# SCH_esp32-8z_230302_2023-04-26.net
KiCad netlist of a schematic drawn in EasyEDA
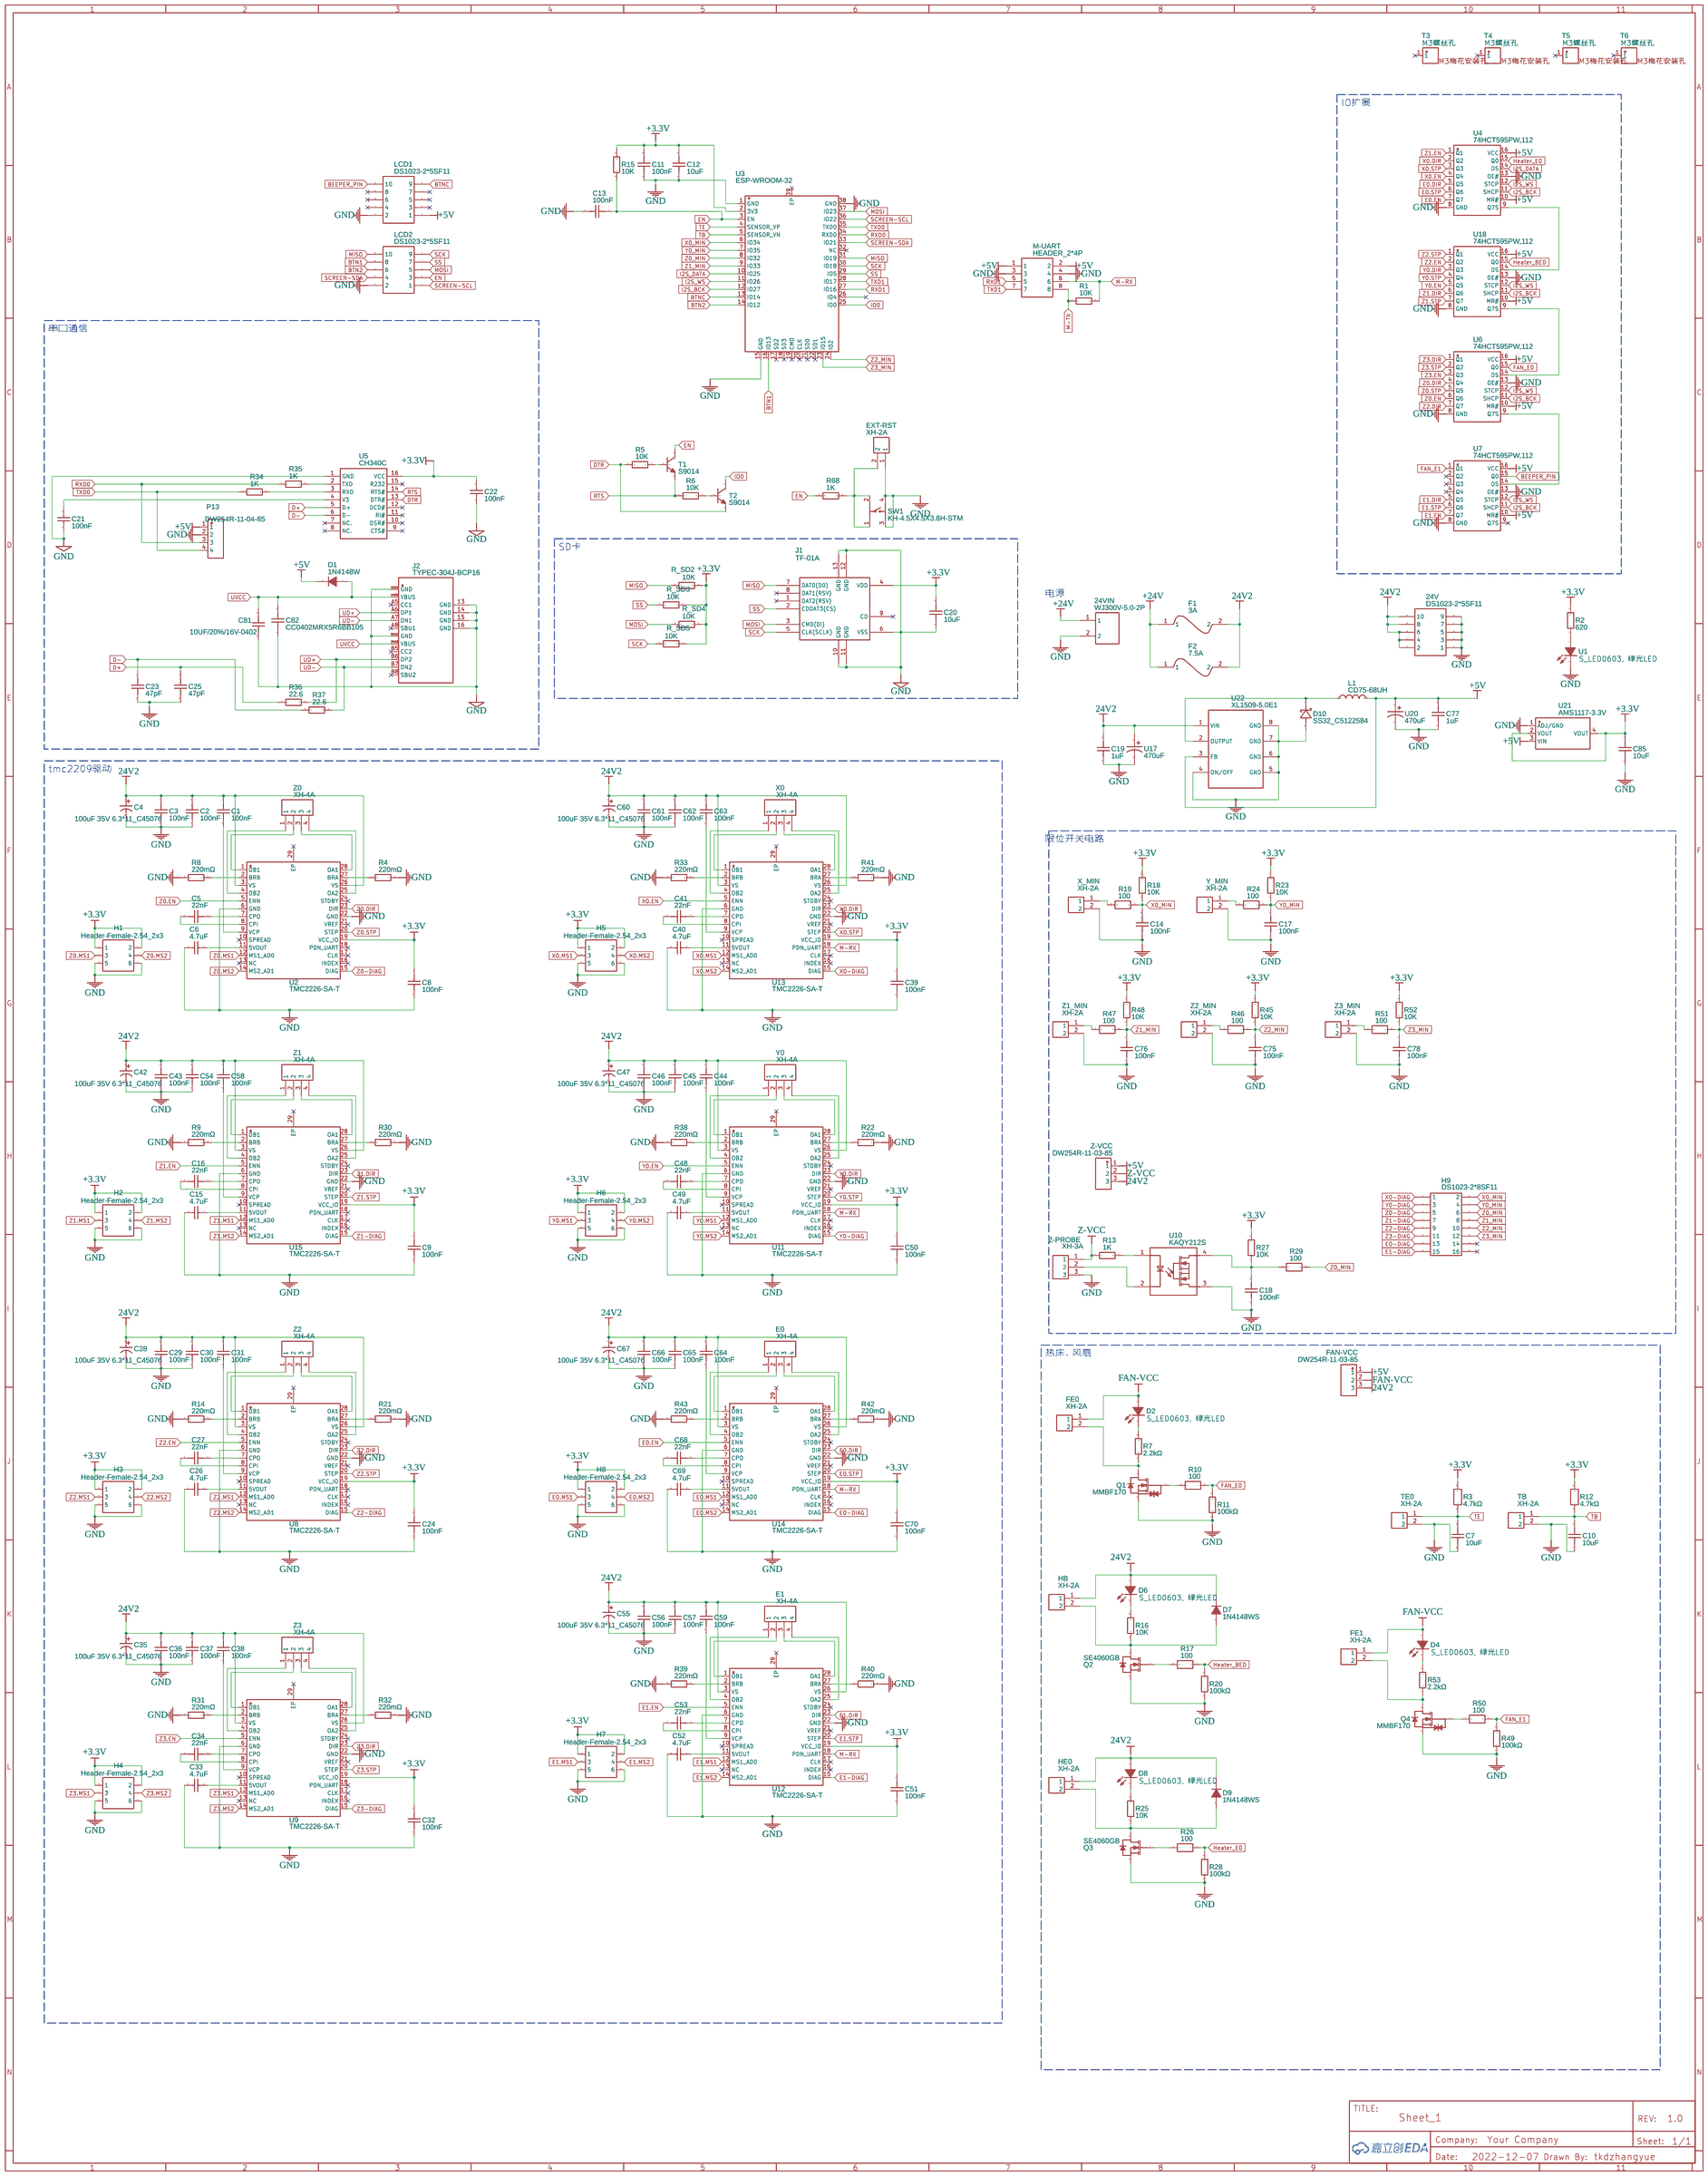
[diagram p0: schematic sheet]

(export (version "E")
  (design (tool "Eeschema 10.0.6"))
  (components
    (comp (ref "24V")
      (value "DS1023-2*5SF11")
      (fields (field (name "BOM_Supplier Part") "C92270"))
      (libsource (lib "") (part "DS1023-2*5SF11_1"))
    )
    (comp (ref "24VIN")
      (value "WJ300V-5.0-2P")
      (fields (field (name "BOM_Supplier Part") "C8385"))
      (libsource (lib "") (part "WJ300V-5.0-2P"))
    )
    (comp (ref "C1")
      (value "100nF")
      (fields
        (field (name "BOM_Manufacturer Part") "06031C104KAT2A")
        (field (name "BOM_Supplier Part") "C2167300")
      )
      (libsource (lib "") (part "06031C104KAT2A_1"))
    )
    (comp (ref "C2")
      (value "100nF")
      (fields
        (field (name "BOM_Manufacturer Part") "06031C104KAT2A")
        (field (name "BOM_Supplier Part") "C2167300")
      )
      (libsource (lib "") (part "06031C104KAT2A"))
    )
    (comp (ref "C3")
      (value "100nF")
      (fields
        (field (name "BOM_Manufacturer Part") "06031C104KAT2A")
        (field (name "BOM_Supplier Part") "C2167300")
      )
      (libsource (lib "") (part "06031C104KAT2A"))
    )
    (comp (ref "C4")
      (value "100uF 35V 6.3*11_C45076")
      (fields
        (field (name "BOM_Manufacturer Part") "100uF 35V 6.3*11")
        (field (name "BOM_Supplier Part") "C45076")
      )
      (libsource (lib "") (part "100uF 35V 6.3*11_C45076"))
    )
    (comp (ref "C5")
      (value "22nF")
      (fields
        (field (name "BOM_Manufacturer Part") "CC0603JRX7R7BB223")
        (field (name "BOM_Supplier Part") "C519532")
      )
      (libsource (lib "") (part "CC0603JRX7R7BB223"))
    )
    (comp (ref "C6")
      (value "4.7uF")
      (fields
        (field (name "BOM_Manufacturer Part") "CC0603KRX5R6BB475")
        (field (name "BOM_Supplier Part") "C109456")
      )
      (libsource (lib "") (part "CC0603KRX5R6BB475"))
    )
    (comp (ref "C7")
      (value "10uF")
      (fields (field (name "BOM_Supplier Part") "C15415"))
      (libsource (lib "") (part "10UF"))
    )
    (comp (ref "C8")
      (value "100nF")
      (fields
        (field (name "BOM_Manufacturer Part") "06031C104KAT2A")
        (field (name "BOM_Supplier Part") "C2167300")
      )
      (libsource (lib "") (part "06031C104KAT2A_1"))
    )
    (comp (ref "C9")
      (value "100nF")
      (fields
        (field (name "BOM_Manufacturer Part") "06031C104KAT2A")
        (field (name "BOM_Supplier Part") "C2167300")
      )
      (libsource (lib "") (part "06031C104KAT2A_1"))
    )
    (comp (ref "C10")
      (value "10uF")
      (fields (field (name "BOM_Supplier Part") "C15415"))
      (libsource (lib "") (part "10UF"))
    )
    (comp (ref "C11")
      (value "100nF")
      (fields
        (field (name "BOM_Manufacturer Part") "06031C104KAT2A")
        (field (name "BOM_Supplier Part") "C2167300")
      )
      (libsource (lib "") (part "06031C104KAT2A"))
    )
    (comp (ref "C12")
      (value "10uF")
      (fields
        (field (name "BOM_Manufacturer Part") "TCC0603X5R106K100CT")
        (field (name "BOM_Supplier Part") "C380314")
      )
      (libsource (lib "") (part "TCC0603X5R106K100CT"))
    )
    (comp (ref "C13")
      (value "100nF")
      (fields
        (field (name "BOM_Manufacturer Part") "06031C104KAT2A")
        (field (name "BOM_Supplier Part") "C2167300")
      )
      (libsource (lib "") (part "06031C104KAT2A_2"))
    )
    (comp (ref "C14")
      (value "100nF")
      (fields
        (field (name "BOM_Manufacturer Part") "06031C104KAT2A")
        (field (name "BOM_Supplier Part") "C2167300")
      )
      (libsource (lib "") (part "06031C104KAT2A"))
    )
    (comp (ref "C15")
      (value "4.7uF")
      (fields
        (field (name "BOM_Manufacturer Part") "CC0603KRX5R6BB475")
        (field (name "BOM_Supplier Part") "C109456")
      )
      (libsource (lib "") (part "CC0603KRX5R6BB475"))
    )
    (comp (ref "C16")
      (value "22nF")
      (fields
        (field (name "BOM_Manufacturer Part") "CC0603JRX7R7BB223")
        (field (name "BOM_Supplier Part") "C519532")
      )
      (libsource (lib "") (part "CC0603JRX7R7BB223"))
    )
    (comp (ref "C17")
      (value "100nF")
      (fields
        (field (name "BOM_Manufacturer Part") "06031C104KAT2A")
        (field (name "BOM_Supplier Part") "C2167300")
      )
      (libsource (lib "") (part "06031C104KAT2A"))
    )
    (comp (ref "C18")
      (value "100nF")
      (fields
        (field (name "BOM_Manufacturer Part") "06031C104KAT2A")
        (field (name "BOM_Supplier Part") "C2167300")
      )
      (libsource (lib "") (part "06031C104KAT2A"))
    )
    (comp (ref "C19")
      (value "1uF")
      (fields
        (field (name "BOM_Manufacturer Part") "0603B105K500NT")
        (field (name "BOM_Supplier Part") "C90540")
      )
      (libsource (lib "") (part "0603B105K500NT"))
    )
    (comp (ref "C20")
      (value "10uF")
      (fields
        (field (name "BOM_Manufacturer Part") "TCC0603X5R106K100CT")
        (field (name "BOM_Supplier Part") "C380314")
      )
      (libsource (lib "") (part "TCC0603X5R106K100CT"))
    )
    (comp (ref "C21")
      (value "100nF")
      (fields
        (field (name "BOM_Manufacturer Part") "0402YD104KAT2A")
        (field (name "BOM_Supplier Part") "C142647")
      )
      (libsource (lib "") (part "0402YD104KAT2A"))
    )
    (comp (ref "C22")
      (value "100nF")
      (fields
        (field (name "BOM_Manufacturer Part") "0402YD104KAT2A")
        (field (name "BOM_Supplier Part") "C142647")
      )
      (libsource (lib "") (part "0402YD104KAT2A"))
    )
    (comp (ref "C23")
      (value "47pF")
      (fields
        (field (name "BOM_Manufacturer Part") "0603N470F101")
        (field (name "BOM_Supplier Part") "C152905")
      )
      (libsource (lib "") (part "0603N470F101"))
    )
    (comp (ref "C24")
      (value "100nF")
      (fields
        (field (name "BOM_Manufacturer Part") "06031C104KAT2A")
        (field (name "BOM_Supplier Part") "C2167300")
      )
      (libsource (lib "") (part "06031C104KAT2A_1"))
    )
    (comp (ref "C25")
      (value "47pF")
      (fields
        (field (name "BOM_Manufacturer Part") "0603N470F101")
        (field (name "BOM_Supplier Part") "C152905")
      )
      (libsource (lib "") (part "0603N470F101"))
    )
    (comp (ref "C26")
      (value "4.7uF")
      (fields
        (field (name "BOM_Manufacturer Part") "CC0603KRX5R6BB475")
        (field (name "BOM_Supplier Part") "C109456")
      )
      (libsource (lib "") (part "CC0603KRX5R6BB475"))
    )
    (comp (ref "C27")
      (value "22nF")
      (fields
        (field (name "BOM_Manufacturer Part") "CC0603JRX7R7BB223")
        (field (name "BOM_Supplier Part") "C519532")
      )
      (libsource (lib "") (part "CC0603JRX7R7BB223"))
    )
    (comp (ref "C28")
      (value "100uF 35V 6.3*11_C45076")
      (fields
        (field (name "BOM_Manufacturer Part") "100uF 35V 6.3*11")
        (field (name "BOM_Supplier Part") "C45076")
      )
      (libsource (lib "") (part "100uF 35V 6.3*11_C45076"))
    )
    (comp (ref "C29")
      (value "100nF")
      (fields
        (field (name "BOM_Manufacturer Part") "06031C104KAT2A")
        (field (name "BOM_Supplier Part") "C2167300")
      )
      (libsource (lib "") (part "06031C104KAT2A"))
    )
    (comp (ref "C30")
      (value "100nF")
      (fields
        (field (name "BOM_Manufacturer Part") "06031C104KAT2A")
        (field (name "BOM_Supplier Part") "C2167300")
      )
      (libsource (lib "") (part "06031C104KAT2A"))
    )
    (comp (ref "C31")
      (value "100nF")
      (fields
        (field (name "BOM_Manufacturer Part") "06031C104KAT2A")
        (field (name "BOM_Supplier Part") "C2167300")
      )
      (libsource (lib "") (part "06031C104KAT2A_1"))
    )
    (comp (ref "C32")
      (value "100nF")
      (fields
        (field (name "BOM_Manufacturer Part") "06031C104KAT2A")
        (field (name "BOM_Supplier Part") "C2167300")
      )
      (libsource (lib "") (part "06031C104KAT2A_1"))
    )
    (comp (ref "C33")
      (value "4.7uF")
      (fields
        (field (name "BOM_Manufacturer Part") "CC0603KRX5R6BB475")
        (field (name "BOM_Supplier Part") "C109456")
      )
      (libsource (lib "") (part "CC0603KRX5R6BB475"))
    )
    (comp (ref "C34")
      (value "22nF")
      (fields
        (field (name "BOM_Manufacturer Part") "CC0603JRX7R7BB223")
        (field (name "BOM_Supplier Part") "C519532")
      )
      (libsource (lib "") (part "CC0603JRX7R7BB223"))
    )
    (comp (ref "C35")
      (value "100uF 35V 6.3*11_C45076")
      (fields
        (field (name "BOM_Manufacturer Part") "100uF 35V 6.3*11")
        (field (name "BOM_Supplier Part") "C45076")
      )
      (libsource (lib "") (part "100uF 35V 6.3*11_C45076"))
    )
    (comp (ref "C36")
      (value "100nF")
      (fields
        (field (name "BOM_Manufacturer Part") "06031C104KAT2A")
        (field (name "BOM_Supplier Part") "C2167300")
      )
      (libsource (lib "") (part "06031C104KAT2A"))
    )
    (comp (ref "C37")
      (value "100nF")
      (fields
        (field (name "BOM_Manufacturer Part") "06031C104KAT2A")
        (field (name "BOM_Supplier Part") "C2167300")
      )
      (libsource (lib "") (part "06031C104KAT2A"))
    )
    (comp (ref "C38")
      (value "100nF")
      (fields
        (field (name "BOM_Manufacturer Part") "06031C104KAT2A")
        (field (name "BOM_Supplier Part") "C2167300")
      )
      (libsource (lib "") (part "06031C104KAT2A_1"))
    )
    (comp (ref "C39")
      (value "100nF")
      (fields
        (field (name "BOM_Manufacturer Part") "06031C104KAT2A")
        (field (name "BOM_Supplier Part") "C2167300")
      )
      (libsource (lib "") (part "06031C104KAT2A_1"))
    )
    (comp (ref "C40")
      (value "4.7uF")
      (fields
        (field (name "BOM_Manufacturer Part") "CC0603KRX5R6BB475")
        (field (name "BOM_Supplier Part") "C109456")
      )
      (libsource (lib "") (part "CC0603KRX5R6BB475"))
    )
    (comp (ref "C41")
      (value "22nF")
      (fields
        (field (name "BOM_Manufacturer Part") "CC0603JRX7R7BB223")
        (field (name "BOM_Supplier Part") "C519532")
      )
      (libsource (lib "") (part "CC0603JRX7R7BB223"))
    )
    (comp (ref "C42")
      (value "100uF 35V 6.3*11_C45076")
      (fields
        (field (name "BOM_Manufacturer Part") "100uF 35V 6.3*11")
        (field (name "BOM_Supplier Part") "C45076")
      )
      (libsource (lib "") (part "100uF 35V 6.3*11_C45076"))
    )
    (comp (ref "C43")
      (value "100nF")
      (fields
        (field (name "BOM_Manufacturer Part") "06031C104KAT2A")
        (field (name "BOM_Supplier Part") "C2167300")
      )
      (libsource (lib "") (part "06031C104KAT2A"))
    )
    (comp (ref "C44")
      (value "100nF")
      (fields
        (field (name "BOM_Manufacturer Part") "06031C104KAT2A")
        (field (name "BOM_Supplier Part") "C2167300")
      )
      (libsource (lib "") (part "06031C104KAT2A_1"))
    )
    (comp (ref "C45")
      (value "100nF")
      (fields
        (field (name "BOM_Manufacturer Part") "06031C104KAT2A")
        (field (name "BOM_Supplier Part") "C2167300")
      )
      (libsource (lib "") (part "06031C104KAT2A"))
    )
    (comp (ref "C46")
      (value "100nF")
      (fields
        (field (name "BOM_Manufacturer Part") "06031C104KAT2A")
        (field (name "BOM_Supplier Part") "C2167300")
      )
      (libsource (lib "") (part "06031C104KAT2A"))
    )
    (comp (ref "C47")
      (value "100uF 35V 6.3*11_C45076")
      (fields
        (field (name "BOM_Manufacturer Part") "100uF 35V 6.3*11")
        (field (name "BOM_Supplier Part") "C45076")
      )
      (libsource (lib "") (part "100uF 35V 6.3*11_C45076"))
    )
    (comp (ref "C48")
      (value "22nF")
      (fields
        (field (name "BOM_Manufacturer Part") "CC0603JRX7R7BB223")
        (field (name "BOM_Supplier Part") "C519532")
      )
      (libsource (lib "") (part "CC0603JRX7R7BB223"))
    )
    (comp (ref "C49")
      (value "4.7uF")
      (fields
        (field (name "BOM_Manufacturer Part") "CC0603KRX5R6BB475")
        (field (name "BOM_Supplier Part") "C109456")
      )
      (libsource (lib "") (part "CC0603KRX5R6BB475"))
    )
    (comp (ref "C50")
      (value "100nF")
      (fields
        (field (name "BOM_Manufacturer Part") "06031C104KAT2A")
        (field (name "BOM_Supplier Part") "C2167300")
      )
      (libsource (lib "") (part "06031C104KAT2A_1"))
    )
    (comp (ref "C51")
      (value "100nF")
      (fields
        (field (name "BOM_Manufacturer Part") "06031C104KAT2A")
        (field (name "BOM_Supplier Part") "C2167300")
      )
      (libsource (lib "") (part "06031C104KAT2A_1"))
    )
    (comp (ref "C52")
      (value "4.7uF")
      (fields
        (field (name "BOM_Manufacturer Part") "CC0603KRX5R6BB475")
        (field (name "BOM_Supplier Part") "C109456")
      )
      (libsource (lib "") (part "CC0603KRX5R6BB475"))
    )
    (comp (ref "C53")
      (value "22nF")
      (fields
        (field (name "BOM_Manufacturer Part") "CC0603JRX7R7BB223")
        (field (name "BOM_Supplier Part") "C519532")
      )
      (libsource (lib "") (part "CC0603JRX7R7BB223"))
    )
    (comp (ref "C54")
      (value "100nF")
      (fields
        (field (name "BOM_Manufacturer Part") "06031C104KAT2A")
        (field (name "BOM_Supplier Part") "C2167300")
      )
      (libsource (lib "") (part "06031C104KAT2A"))
    )
    (comp (ref "C55")
      (value "100uF 35V 6.3*11_C45076")
      (fields
        (field (name "BOM_Manufacturer Part") "100uF 35V 6.3*11")
        (field (name "BOM_Supplier Part") "C45076")
      )
      (libsource (lib "") (part "100uF 35V 6.3*11_C45076"))
    )
    (comp (ref "C56")
      (value "100nF")
      (fields
        (field (name "BOM_Manufacturer Part") "06031C104KAT2A")
        (field (name "BOM_Supplier Part") "C2167300")
      )
      (libsource (lib "") (part "06031C104KAT2A"))
    )
    (comp (ref "C57")
      (value "100nF")
      (fields
        (field (name "BOM_Manufacturer Part") "06031C104KAT2A")
        (field (name "BOM_Supplier Part") "C2167300")
      )
      (libsource (lib "") (part "06031C104KAT2A"))
    )
    (comp (ref "C58")
      (value "100nF")
      (fields
        (field (name "BOM_Manufacturer Part") "06031C104KAT2A")
        (field (name "BOM_Supplier Part") "C2167300")
      )
      (libsource (lib "") (part "06031C104KAT2A_1"))
    )
    (comp (ref "C59")
      (value "100nF")
      (fields
        (field (name "BOM_Manufacturer Part") "06031C104KAT2A")
        (field (name "BOM_Supplier Part") "C2167300")
      )
      (libsource (lib "") (part "06031C104KAT2A_1"))
    )
    (comp (ref "C60")
      (value "100uF 35V 6.3*11_C45076")
      (fields
        (field (name "BOM_Manufacturer Part") "100uF 35V 6.3*11")
        (field (name "BOM_Supplier Part") "C45076")
      )
      (libsource (lib "") (part "100uF 35V 6.3*11_C45076"))
    )
    (comp (ref "C61")
      (value "100nF")
      (fields
        (field (name "BOM_Manufacturer Part") "06031C104KAT2A")
        (field (name "BOM_Supplier Part") "C2167300")
      )
      (libsource (lib "") (part "06031C104KAT2A"))
    )
    (comp (ref "C62")
      (value "100nF")
      (fields
        (field (name "BOM_Manufacturer Part") "06031C104KAT2A")
        (field (name "BOM_Supplier Part") "C2167300")
      )
      (libsource (lib "") (part "06031C104KAT2A"))
    )
    (comp (ref "C63")
      (value "100nF")
      (fields
        (field (name "BOM_Manufacturer Part") "06031C104KAT2A")
        (field (name "BOM_Supplier Part") "C2167300")
      )
      (libsource (lib "") (part "06031C104KAT2A_1"))
    )
    (comp (ref "C64")
      (value "100nF")
      (fields
        (field (name "BOM_Manufacturer Part") "06031C104KAT2A")
        (field (name "BOM_Supplier Part") "C2167300")
      )
      (libsource (lib "") (part "06031C104KAT2A_1"))
    )
    (comp (ref "C65")
      (value "100nF")
      (fields
        (field (name "BOM_Manufacturer Part") "06031C104KAT2A")
        (field (name "BOM_Supplier Part") "C2167300")
      )
      (libsource (lib "") (part "06031C104KAT2A"))
    )
    (comp (ref "C66")
      (value "100nF")
      (fields
        (field (name "BOM_Manufacturer Part") "06031C104KAT2A")
        (field (name "BOM_Supplier Part") "C2167300")
      )
      (libsource (lib "") (part "06031C104KAT2A"))
    )
    (comp (ref "C67")
      (value "100uF 35V 6.3*11_C45076")
      (fields
        (field (name "BOM_Manufacturer Part") "100uF 35V 6.3*11")
        (field (name "BOM_Supplier Part") "C45076")
      )
      (libsource (lib "") (part "100uF 35V 6.3*11_C45076"))
    )
    (comp (ref "C68")
      (value "22nF")
      (fields
        (field (name "BOM_Manufacturer Part") "CC0603JRX7R7BB223")
        (field (name "BOM_Supplier Part") "C519532")
      )
      (libsource (lib "") (part "CC0603JRX7R7BB223"))
    )
    (comp (ref "C69")
      (value "4.7uF")
      (fields
        (field (name "BOM_Manufacturer Part") "CC0603KRX5R6BB475")
        (field (name "BOM_Supplier Part") "C109456")
      )
      (libsource (lib "") (part "CC0603KRX5R6BB475"))
    )
    (comp (ref "C70")
      (value "100nF")
      (fields
        (field (name "BOM_Manufacturer Part") "06031C104KAT2A")
        (field (name "BOM_Supplier Part") "C2167300")
      )
      (libsource (lib "") (part "06031C104KAT2A_1"))
    )
    (comp (ref "C75")
      (value "100nF")
      (fields
        (field (name "BOM_Manufacturer Part") "06031C104KAT2A")
        (field (name "BOM_Supplier Part") "C2167300")
      )
      (libsource (lib "") (part "06031C104KAT2A"))
    )
    (comp (ref "C76")
      (value "100nF")
      (fields
        (field (name "BOM_Manufacturer Part") "06031C104KAT2A")
        (field (name "BOM_Supplier Part") "C2167300")
      )
      (libsource (lib "") (part "06031C104KAT2A"))
    )
    (comp (ref "C77")
      (value "1uF")
      (fields
        (field (name "BOM_Manufacturer Part") "0603B105K500NT")
        (field (name "BOM_Supplier Part") "C90540")
      )
      (libsource (lib "") (part "0603B105K500NT"))
    )
    (comp (ref "C78")
      (value "100nF")
      (fields
        (field (name "BOM_Manufacturer Part") "06031C104KAT2A")
        (field (name "BOM_Supplier Part") "C2167300")
      )
      (libsource (lib "") (part "06031C104KAT2A"))
    )
    (comp (ref "C81")
      (value "10UF/20%/16V-0402")
      (fields
        (field (name "BOM_Manufacturer Part") "10uF/20%/16V-0402")
        (field (name "BOM_Supplier Part") "C9900005775")
      )
      (libsource (lib "") (part "10UF/20%/16V-0402"))
    )
    (comp (ref "C82")
      (value "CC0402MRX5R6BB105")
      (fields (field (name "BOM_Supplier Part") "C113791"))
      (libsource (lib "") (part "CC0402MRX5R6BB105"))
    )
    (comp (ref "C85")
      (value "10uF")
      (fields
        (field (name "BOM_Manufacturer Part") "TCC0603X5R106K100CT")
        (field (name "BOM_Supplier Part") "C380314")
      )
      (libsource (lib "") (part "TCC0603X5R106K100CT"))
    )
    (comp (ref "D1")
      (value "1N4148W")
      (fields (field (name "BOM_Supplier Part") "C179717"))
      (libsource (lib "") (part "1N4148W"))
    )
    (comp (ref "D2")
      (value "S_LED0603, 绿光LED")
      (fields (field (name "BOM_Supplier Part") "C9900025458"))
      (libsource (lib "") (part "S_LED0603, 绿光LED_1"))
    )
    (comp (ref "D4")
      (value "S_LED0603, 绿光LED")
      (fields (field (name "BOM_Supplier Part") "C9900025458"))
      (libsource (lib "") (part "S_LED0603, 绿光LED_1"))
    )
    (comp (ref "D6")
      (value "S_LED0603, 绿光LED")
      (fields (field (name "BOM_Supplier Part") "C9900025458"))
      (libsource (lib "") (part "S_LED0603, 绿光LED_1"))
    )
    (comp (ref "D7")
      (value "1N4148WS")
      (fields (field (name "BOM_Supplier Part") "C179718"))
      (libsource (lib "") (part "1N4148WS"))
    )
    (comp (ref "D8")
      (value "S_LED0603, 绿光LED")
      (fields (field (name "BOM_Supplier Part") "C9900025458"))
      (libsource (lib "") (part "S_LED0603, 绿光LED_1"))
    )
    (comp (ref "D9")
      (value "1N4148WS")
      (fields (field (name "BOM_Supplier Part") "C179718"))
      (libsource (lib "") (part "1N4148WS"))
    )
    (comp (ref "D10")
      (value "SS32_C5122584")
      (fields (field (name "BOM_Manufacturer Part") "SS32") (field (name "BOM_Supplier Part") "C5122584"))
      (libsource (lib "") (part "SS32_C5122584"))
    )
    (comp (ref "E0")
      (value "XH-4A")
      (fields (field (name "BOM_Supplier Part") "C37815"))
      (libsource (lib "") (part "XH-4A_3"))
    )
    (comp (ref "E1")
      (value "XH-4A")
      (fields (field (name "BOM_Supplier Part") "C37815"))
      (libsource (lib "") (part "XH-4A_3"))
    )
    (comp (ref "EXT-RST")
      (value "XH-2A")
      (fields (field (name "BOM_Supplier Part") "C20079"))
      (libsource (lib "") (part "XH-2A_6"))
    )
    (comp (ref "F1") (value "3A") (libsource (lib "") (part "小型汽车插片保险座")))
    (comp (ref "F2") (value "7.5A") (libsource (lib "") (part "小型汽车插片保险座")))
    (comp (ref "FAN-VCC")
      (value "DW254R-11-03-85")
      (fields (field (name "BOM_Supplier Part") "C2935897"))
      (libsource (lib "") (part "DW254R-11-03-85"))
    )
    (comp (ref "FE0")
      (value "XH-2A")
      (fields (field (name "BOM_Supplier Part") "C20079"))
      (libsource (lib "") (part "XH-2A"))
    )
    (comp (ref "FE1")
      (value "XH-2A")
      (fields (field (name "BOM_Supplier Part") "C20079"))
      (libsource (lib "") (part "XH-2A"))
    )
    (comp (ref "H1")
      (value "Header-Female-2.54_2x3")
      (fields
        (field (name "BOM_Manufacturer Part") "DS1023-2*3SF11")
        (field (name "BOM_Supplier Part") "C92272")
      )
      (libsource (lib "") (part "Header-Female-2.54_2x3"))
    )
    (comp (ref "H2")
      (value "Header-Female-2.54_2x3")
      (fields
        (field (name "BOM_Manufacturer Part") "DS1023-2*3SF11")
        (field (name "BOM_Supplier Part") "C92272")
      )
      (libsource (lib "") (part "Header-Female-2.54_2x3"))
    )
    (comp (ref "H3")
      (value "Header-Female-2.54_2x3")
      (fields
        (field (name "BOM_Manufacturer Part") "DS1023-2*3SF11")
        (field (name "BOM_Supplier Part") "C92272")
      )
      (libsource (lib "") (part "Header-Female-2.54_2x3"))
    )
    (comp (ref "H4")
      (value "Header-Female-2.54_2x3")
      (fields
        (field (name "BOM_Manufacturer Part") "DS1023-2*3SF11")
        (field (name "BOM_Supplier Part") "C92272")
      )
      (libsource (lib "") (part "Header-Female-2.54_2x3"))
    )
    (comp (ref "H5")
      (value "Header-Female-2.54_2x3")
      (fields
        (field (name "BOM_Manufacturer Part") "DS1023-2*3SF11")
        (field (name "BOM_Supplier Part") "C92272")
      )
      (libsource (lib "") (part "Header-Female-2.54_2x3"))
    )
    (comp (ref "H6")
      (value "Header-Female-2.54_2x3")
      (fields
        (field (name "BOM_Manufacturer Part") "DS1023-2*3SF11")
        (field (name "BOM_Supplier Part") "C92272")
      )
      (libsource (lib "") (part "Header-Female-2.54_2x3"))
    )
    (comp (ref "H7")
      (value "Header-Female-2.54_2x3")
      (fields
        (field (name "BOM_Manufacturer Part") "DS1023-2*3SF11")
        (field (name "BOM_Supplier Part") "C92272")
      )
      (libsource (lib "") (part "Header-Female-2.54_2x3"))
    )
    (comp (ref "H8")
      (value "Header-Female-2.54_2x3")
      (fields
        (field (name "BOM_Manufacturer Part") "DS1023-2*3SF11")
        (field (name "BOM_Supplier Part") "C92272")
      )
      (libsource (lib "") (part "Header-Female-2.54_2x3"))
    )
    (comp (ref "H9")
      (value "DS1023-2*8SF11")
      (fields (field (name "BOM_Supplier Part") "C92267"))
      (libsource (lib "") (part "DS1023-2*8SF11"))
    )
    (comp (ref "HB")
      (value "XH-2A")
      (fields (field (name "BOM_Supplier Part") "C20079"))
      (libsource (lib "") (part "XH-2A_4"))
    )
    (comp (ref "HE0")
      (value "XH-2A")
      (fields (field (name "BOM_Supplier Part") "C20079"))
      (libsource (lib "") (part "XH-2A_7"))
    )
    (comp (ref "J1")
      (value "TF-01A")
      (fields (field (name "BOM_Supplier Part") "C91145"))
      (libsource (lib "") (part "TF-01A"))
    )
    (comp (ref "J2")
      (value "TYPEC-304J-BCP16")
      (fields (field (name "BOM_Supplier Part") "C2835315"))
      (libsource (lib "") (part "TYPEC-304J-BCP16"))
    )
    (comp (ref "L1")
      (value "CD75-68UH")
      (fields (field (name "BOM_Supplier Part") "C2836693"))
      (libsource (lib "") (part "CD75-68UH"))
    )
    (comp (ref "LCD1")
      (value "DS1023-2*5SF11")
      (fields (field (name "BOM_Supplier Part") "C92270"))
      (libsource (lib "") (part "DS1023-2*5SF11"))
    )
    (comp (ref "LCD2")
      (value "DS1023-2*5SF11")
      (fields (field (name "BOM_Supplier Part") "C92270"))
      (libsource (lib "") (part "DS1023-2*5SF11"))
    )
    (comp (ref "M-UART")
      (value "HEADER_2*4P")
      (fields (field (name "BOM_Supplier Part") "C9900003187"))
      (libsource (lib "") (part "HEADER_2*4P"))
    )
    (comp (ref "P13")
      (value "DW254R-11-04-85")
      (fields (field (name "BOM_Supplier Part") "C2935898"))
      (libsource (lib "") (part "DW254R-11-04-85"))
    )
    (comp (ref "Q1")
      (value "MMBF170")
      (fields (field (name "BOM_Supplier Part") "C130879"))
      (libsource (lib "") (part "MMBF170"))
    )
    (comp (ref "Q2")
      (value "SE4060GB")
      (fields (field (name "BOM_Supplier Part") "C238624"))
      (libsource (lib "") (part "SE4060GB"))
    )
    (comp (ref "Q3")
      (value "SE4060GB")
      (fields (field (name "BOM_Supplier Part") "C238624"))
      (libsource (lib "") (part "SE4060GB"))
    )
    (comp (ref "Q4")
      (value "MMBF170")
      (fields (field (name "BOM_Supplier Part") "C130879"))
      (libsource (lib "") (part "MMBF170"))
    )
    (comp (ref "R1")
      (value "10K")
      (fields
        (field (name "BOM_Manufacturer Part") "AF0603JR-0710KL")
        (field (name "BOM_Supplier Part") "C144116")
      )
      (libsource (lib "") (part "AF0603JR-0710KL_1"))
    )
    (comp (ref "R2")
      (value "620")
      (fields
        (field (name "BOM_Manufacturer Part") "RC0603JR-07620RL")
        (field (name "BOM_Supplier Part") "C137616")
      )
      (libsource (lib "") (part "RC0603JR-07620RL"))
    )
    (comp (ref "R3")
      (value "4.7kΩ")
      (fields
        (field (name "BOM_Manufacturer Part") "RT0603FRE074K7L")
        (field (name "BOM_Supplier Part") "C700513")
      )
      (libsource (lib "") (part "RT0603FRE074K7L"))
    )
    (comp (ref "R4")
      (value "220mΩ")
      (fields
        (field (name "BOM_Manufacturer Part") "CR0603FR220P05Z")
        (field (name "BOM_Supplier Part") "C175648")
      )
      (libsource (lib "") (part "CR0603F0R22P05"))
    )
    (comp (ref "R5")
      (value "10K")
      (fields
        (field (name "BOM_Manufacturer Part") "AF0603JR-0710KL")
        (field (name "BOM_Supplier Part") "C144116")
      )
      (libsource (lib "") (part "AF0603JR-0710KL_1"))
    )
    (comp (ref "R6")
      (value "10K")
      (fields
        (field (name "BOM_Manufacturer Part") "AF0603JR-0710KL")
        (field (name "BOM_Supplier Part") "C144116")
      )
      (libsource (lib "") (part "AF0603JR-0710KL_1"))
    )
    (comp (ref "R7")
      (value "2.2kΩ")
      (fields
        (field (name "BOM_Manufacturer Part") "RMC06032.2K1%N")
        (field (name "BOM_Supplier Part") "C325591")
      )
      (libsource (lib "") (part "RMC06032.2K1%N"))
    )
    (comp (ref "R8")
      (value "220mΩ")
      (fields
        (field (name "BOM_Manufacturer Part") "CR0603FR220P05Z")
        (field (name "BOM_Supplier Part") "C175648")
      )
      (libsource (lib "") (part "CR0603F0R22P05"))
    )
    (comp (ref "R9")
      (value "220mΩ")
      (fields
        (field (name "BOM_Manufacturer Part") "CR0603FR220P05Z")
        (field (name "BOM_Supplier Part") "C175648")
      )
      (libsource (lib "") (part "CR0603F0R22P05"))
    )
    (comp (ref "R10")
      (value "100")
      (fields
        (field (name "BOM_Manufacturer Part") "AC0603DR-07100RL")
        (field (name "BOM_Supplier Part") "C227435")
      )
      (libsource (lib "") (part "AC0603DR-07100RL"))
    )
    (comp (ref "R11")
      (value "100kΩ")
      (fields
        (field (name "BOM_Manufacturer Part") "RMCF0603FT100K")
        (field (name "BOM_Supplier Part") "C237792")
      )
      (libsource (lib "") (part "RMCF0603FT100K"))
    )
    (comp (ref "R12")
      (value "4.7kΩ")
      (fields
        (field (name "BOM_Manufacturer Part") "RT0603FRE074K7L")
        (field (name "BOM_Supplier Part") "C700513")
      )
      (libsource (lib "") (part "RT0603FRE074K7L"))
    )
    (comp (ref "R13")
      (value "1K")
      (fields
        (field (name "BOM_Manufacturer Part") "RT0603FRD071KL")
        (field (name "BOM_Supplier Part") "C136938")
      )
      (libsource (lib "") (part "RT0603FRD071KL"))
    )
    (comp (ref "R14")
      (value "220mΩ")
      (fields
        (field (name "BOM_Manufacturer Part") "CR0603FR220P05Z")
        (field (name "BOM_Supplier Part") "C175648")
      )
      (libsource (lib "") (part "CR0603F0R22P05"))
    )
    (comp (ref "R15")
      (value "10K")
      (fields
        (field (name "BOM_Manufacturer Part") "AF0603JR-0710KL")
        (field (name "BOM_Supplier Part") "C144116")
      )
      (libsource (lib "") (part "AF0603JR-0710KL_2"))
    )
    (comp (ref "R16")
      (value "10K")
      (fields
        (field (name "BOM_Manufacturer Part") "AF0603JR-0710KL")
        (field (name "BOM_Supplier Part") "C144116")
      )
      (libsource (lib "") (part "AF0603JR-0710KL_2"))
    )
    (comp (ref "R17")
      (value "100")
      (fields
        (field (name "BOM_Manufacturer Part") "AC0603DR-07100RL")
        (field (name "BOM_Supplier Part") "C227435")
      )
      (libsource (lib "") (part "AC0603DR-07100RL"))
    )
    (comp (ref "R18")
      (value "10K")
      (fields
        (field (name "BOM_Manufacturer Part") "AF0603JR-0710KL")
        (field (name "BOM_Supplier Part") "C144116")
      )
      (libsource (lib "") (part "AF0603JR-0710KL"))
    )
    (comp (ref "R19")
      (value "100")
      (fields
        (field (name "BOM_Manufacturer Part") "AC0603DR-07100RL")
        (field (name "BOM_Supplier Part") "C227435")
      )
      (libsource (lib "") (part "AC0603DR-07100RL"))
    )
    (comp (ref "R20")
      (value "100kΩ")
      (fields
        (field (name "BOM_Manufacturer Part") "RMCF0603FT100K")
        (field (name "BOM_Supplier Part") "C237792")
      )
      (libsource (lib "") (part "RMCF0603FT100K"))
    )
    (comp (ref "R21")
      (value "220mΩ")
      (fields
        (field (name "BOM_Manufacturer Part") "CR0603FR220P05Z")
        (field (name "BOM_Supplier Part") "C175648")
      )
      (libsource (lib "") (part "CR0603F0R22P05"))
    )
    (comp (ref "R22")
      (value "220mΩ")
      (fields
        (field (name "BOM_Manufacturer Part") "CR0603FR220P05Z")
        (field (name "BOM_Supplier Part") "C175648")
      )
      (libsource (lib "") (part "CR0603F0R22P05"))
    )
    (comp (ref "R23")
      (value "10K")
      (fields
        (field (name "BOM_Manufacturer Part") "AF0603JR-0710KL")
        (field (name "BOM_Supplier Part") "C144116")
      )
      (libsource (lib "") (part "AF0603JR-0710KL"))
    )
    (comp (ref "R24")
      (value "100")
      (fields
        (field (name "BOM_Manufacturer Part") "AC0603DR-07100RL")
        (field (name "BOM_Supplier Part") "C227435")
      )
      (libsource (lib "") (part "AC0603DR-07100RL"))
    )
    (comp (ref "R25")
      (value "10K")
      (fields
        (field (name "BOM_Manufacturer Part") "AF0603JR-0710KL")
        (field (name "BOM_Supplier Part") "C144116")
      )
      (libsource (lib "") (part "AF0603JR-0710KL_2"))
    )
    (comp (ref "R26")
      (value "100")
      (fields
        (field (name "BOM_Manufacturer Part") "AC0603DR-07100RL")
        (field (name "BOM_Supplier Part") "C227435")
      )
      (libsource (lib "") (part "AC0603DR-07100RL"))
    )
    (comp (ref "R27")
      (value "10K")
      (fields
        (field (name "BOM_Manufacturer Part") "AF0603JR-0710KL")
        (field (name "BOM_Supplier Part") "C144116")
      )
      (libsource (lib "") (part "AF0603JR-0710KL_2"))
    )
    (comp (ref "R28")
      (value "100kΩ")
      (fields
        (field (name "BOM_Manufacturer Part") "RMCF0603FT100K")
        (field (name "BOM_Supplier Part") "C237792")
      )
      (libsource (lib "") (part "RMCF0603FT100K"))
    )
    (comp (ref "R29")
      (value "100")
      (fields
        (field (name "BOM_Manufacturer Part") "AC0603DR-07100RL")
        (field (name "BOM_Supplier Part") "C227435")
      )
      (libsource (lib "") (part "AC0603DR-07100RL"))
    )
    (comp (ref "R30")
      (value "220mΩ")
      (fields
        (field (name "BOM_Manufacturer Part") "CR0603FR220P05Z")
        (field (name "BOM_Supplier Part") "C175648")
      )
      (libsource (lib "") (part "CR0603F0R22P05"))
    )
    (comp (ref "R31")
      (value "220mΩ")
      (fields
        (field (name "BOM_Manufacturer Part") "CR0603FR220P05Z")
        (field (name "BOM_Supplier Part") "C175648")
      )
      (libsource (lib "") (part "CR0603F0R22P05"))
    )
    (comp (ref "R32")
      (value "220mΩ")
      (fields
        (field (name "BOM_Manufacturer Part") "CR0603FR220P05Z")
        (field (name "BOM_Supplier Part") "C175648")
      )
      (libsource (lib "") (part "CR0603F0R22P05"))
    )
    (comp (ref "R33")
      (value "220mΩ")
      (fields
        (field (name "BOM_Manufacturer Part") "CR0603FR220P05Z")
        (field (name "BOM_Supplier Part") "C175648")
      )
      (libsource (lib "") (part "CR0603F0R22P05"))
    )
    (comp (ref "R34")
      (value "1K")
      (fields
        (field (name "BOM_Manufacturer Part") "RC0603JR-071KL")
        (field (name "BOM_Supplier Part") "C14676")
      )
      (libsource (lib "") (part "RC0603JR-071KL"))
    )
    (comp (ref "R35")
      (value "1K")
      (fields
        (field (name "BOM_Manufacturer Part") "RC0603JR-071KL")
        (field (name "BOM_Supplier Part") "C14676")
      )
      (libsource (lib "") (part "RC0603JR-071KL"))
    )
    (comp (ref "R36")
      (value "22.6")
      (fields
        (field (name "BOM_Manufacturer Part") "AC0603FR-0722R6L")
        (field (name "BOM_Supplier Part") "C227718")
      )
      (libsource (lib "") (part "AC0603FR-0722R6L"))
    )
    (comp (ref "R37")
      (value "22.6")
      (fields
        (field (name "BOM_Manufacturer Part") "AC0603FR-0722R6L")
        (field (name "BOM_Supplier Part") "C227718")
      )
      (libsource (lib "") (part "AC0603FR-0722R6L"))
    )
    (comp (ref "R38")
      (value "220mΩ")
      (fields
        (field (name "BOM_Manufacturer Part") "CR0603FR220P05Z")
        (field (name "BOM_Supplier Part") "C175648")
      )
      (libsource (lib "") (part "CR0603F0R22P05"))
    )
    (comp (ref "R39")
      (value "220mΩ")
      (fields
        (field (name "BOM_Manufacturer Part") "CR0603FR220P05Z")
        (field (name "BOM_Supplier Part") "C175648")
      )
      (libsource (lib "") (part "CR0603F0R22P05"))
    )
    (comp (ref "R40")
      (value "220mΩ")
      (fields
        (field (name "BOM_Manufacturer Part") "CR0603FR220P05Z")
        (field (name "BOM_Supplier Part") "C175648")
      )
      (libsource (lib "") (part "CR0603F0R22P05"))
    )
    (comp (ref "R41")
      (value "220mΩ")
      (fields
        (field (name "BOM_Manufacturer Part") "CR0603FR220P05Z")
        (field (name "BOM_Supplier Part") "C175648")
      )
      (libsource (lib "") (part "CR0603F0R22P05"))
    )
    (comp (ref "R42")
      (value "220mΩ")
      (fields
        (field (name "BOM_Manufacturer Part") "CR0603FR220P05Z")
        (field (name "BOM_Supplier Part") "C175648")
      )
      (libsource (lib "") (part "CR0603F0R22P05"))
    )
    (comp (ref "R43")
      (value "220mΩ")
      (fields
        (field (name "BOM_Manufacturer Part") "CR0603FR220P05Z")
        (field (name "BOM_Supplier Part") "C175648")
      )
      (libsource (lib "") (part "CR0603F0R22P05"))
    )
    (comp (ref "R45")
      (value "10K")
      (fields
        (field (name "BOM_Manufacturer Part") "AF0603JR-0710KL")
        (field (name "BOM_Supplier Part") "C144116")
      )
      (libsource (lib "") (part "AF0603JR-0710KL"))
    )
    (comp (ref "R46")
      (value "100")
      (fields
        (field (name "BOM_Manufacturer Part") "AC0603DR-07100RL")
        (field (name "BOM_Supplier Part") "C227435")
      )
      (libsource (lib "") (part "AC0603DR-07100RL"))
    )
    (comp (ref "R47")
      (value "100")
      (fields
        (field (name "BOM_Manufacturer Part") "AC0603DR-07100RL")
        (field (name "BOM_Supplier Part") "C227435")
      )
      (libsource (lib "") (part "AC0603DR-07100RL"))
    )
    (comp (ref "R48")
      (value "10K")
      (fields
        (field (name "BOM_Manufacturer Part") "AF0603JR-0710KL")
        (field (name "BOM_Supplier Part") "C144116")
      )
      (libsource (lib "") (part "AF0603JR-0710KL"))
    )
    (comp (ref "R49")
      (value "100kΩ")
      (fields
        (field (name "BOM_Manufacturer Part") "RMCF0603FT100K")
        (field (name "BOM_Supplier Part") "C237792")
      )
      (libsource (lib "") (part "RMCF0603FT100K"))
    )
    (comp (ref "R50")
      (value "100")
      (fields
        (field (name "BOM_Manufacturer Part") "AC0603DR-07100RL")
        (field (name "BOM_Supplier Part") "C227435")
      )
      (libsource (lib "") (part "AC0603DR-07100RL"))
    )
    (comp (ref "R51")
      (value "100")
      (fields
        (field (name "BOM_Manufacturer Part") "AC0603DR-07100RL")
        (field (name "BOM_Supplier Part") "C227435")
      )
      (libsource (lib "") (part "AC0603DR-07100RL"))
    )
    (comp (ref "R52")
      (value "10K")
      (fields
        (field (name "BOM_Manufacturer Part") "AF0603JR-0710KL")
        (field (name "BOM_Supplier Part") "C144116")
      )
      (libsource (lib "") (part "AF0603JR-0710KL"))
    )
    (comp (ref "R53")
      (value "2.2kΩ")
      (fields
        (field (name "BOM_Manufacturer Part") "RMC06032.2K1%N")
        (field (name "BOM_Supplier Part") "C325591")
      )
      (libsource (lib "") (part "RMC06032.2K1%N"))
    )
    (comp (ref "R68")
      (value "1K")
      (fields
        (field (name "BOM_Manufacturer Part") "RT0603FRD071KL")
        (field (name "BOM_Supplier Part") "C136938")
      )
      (libsource (lib "") (part "RT0603FRD071KL"))
    )
    (comp (ref "R_SD2")
      (value "10K")
      (fields
        (field (name "BOM_Manufacturer Part") "AF0603JR-0710KL")
        (field (name "BOM_Supplier Part") "C144116")
      )
      (libsource (lib "") (part "AF0603JR-0710KL_3"))
    )
    (comp (ref "R_SD3")
      (value "10K")
      (fields
        (field (name "BOM_Manufacturer Part") "AF0603JR-0710KL")
        (field (name "BOM_Supplier Part") "C144116")
      )
      (libsource (lib "") (part "AF0603JR-0710KL_3"))
    )
    (comp (ref "R_SD4")
      (value "10K")
      (fields
        (field (name "BOM_Manufacturer Part") "AF0603JR-0710KL")
        (field (name "BOM_Supplier Part") "C144116")
      )
      (libsource (lib "") (part "AF0603JR-0710KL_3"))
    )
    (comp (ref "R_SD5")
      (value "10K")
      (fields
        (field (name "BOM_Manufacturer Part") "AF0603JR-0710KL")
        (field (name "BOM_Supplier Part") "C144116")
      )
      (libsource (lib "") (part "AF0603JR-0710KL_3"))
    )
    (comp (ref "SW1")
      (value "KH-4.5X4.5X3.8H-STM")
      (fields (field (name "BOM_Supplier Part") "C2837549"))
      (libsource (lib "") (part "KH-4.5X4.5X3.8H-STM"))
    )
    (comp (ref "T1")
      (value "S9014")
      (fields (field (name "BOM_Supplier Part") "C181164"))
      (libsource (lib "") (part "S9014"))
    )
    (comp (ref "T2")
      (value "S9014")
      (fields (field (name "BOM_Supplier Part") "C181164"))
      (libsource (lib "") (part "S9014"))
    )
    (comp (ref "T3") (value "M3螺丝孔") (libsource (lib "") (part "M3螺丝孔")))
    (comp (ref "T4") (value "M3螺丝孔") (libsource (lib "") (part "M3螺丝孔")))
    (comp (ref "T5") (value "M3螺丝孔") (libsource (lib "") (part "M3螺丝孔")))
    (comp (ref "T6") (value "M3螺丝孔") (libsource (lib "") (part "M3螺丝孔")))
    (comp (ref "TB")
      (value "XH-2A")
      (fields (field (name "BOM_Supplier Part") "C20079"))
      (libsource (lib "") (part "XH-2A_10"))
    )
    (comp (ref "TE0")
      (value "XH-2A")
      (fields (field (name "BOM_Supplier Part") "C20079"))
      (libsource (lib "") (part "XH-2A_2"))
    )
    (comp (ref "U1")
      (value "S_LED0603, 绿光LED")
      (fields (field (name "BOM_Supplier Part") "C9900025458"))
      (libsource (lib "") (part "S_LED0603, 绿光LED"))
    )
    (comp (ref "U2")
      (value "TMC2226-SA-T")
      (fields (field (name "BOM_Supplier Part") "C705366"))
      (libsource (lib "") (part "TMC2226-SA-T"))
    )
    (comp (ref "U3")
      (value "ESP-WROOM-32")
      (fields (field (name "BOM_Supplier Part") "C95209"))
      (libsource (lib "") (part "ESP-WROOM-32"))
    )
    (comp (ref "U4")
      (value "74HCT595PW,112")
      (fields (field (name "BOM_Supplier Part") "C547810"))
      (libsource (lib "") (part "74HCT595PW,112"))
    )
    (comp (ref "U5")
      (value "CH340C")
      (fields (field (name "BOM_Supplier Part") "C84681"))
      (libsource (lib "") (part "CH340C"))
    )
    (comp (ref "U6")
      (value "74HCT595PW,112")
      (fields (field (name "BOM_Supplier Part") "C547810"))
      (libsource (lib "") (part "74HCT595PW,112"))
    )
    (comp (ref "U7")
      (value "74HCT595PW,112")
      (fields (field (name "BOM_Supplier Part") "C547810"))
      (libsource (lib "") (part "74HCT595PW,112"))
    )
    (comp (ref "U8")
      (value "TMC2226-SA-T")
      (fields (field (name "BOM_Supplier Part") "C705366"))
      (libsource (lib "") (part "TMC2226-SA-T"))
    )
    (comp (ref "U9")
      (value "TMC2226-SA-T")
      (fields (field (name "BOM_Supplier Part") "C705366"))
      (libsource (lib "") (part "TMC2226-SA-T"))
    )
    (comp (ref "U10")
      (value "KAQY212S")
      (fields (field (name "BOM_Supplier Part") "C194898"))
      (libsource (lib "") (part "KAQY212S"))
    )
    (comp (ref "U11")
      (value "TMC2226-SA-T")
      (fields (field (name "BOM_Supplier Part") "C705366"))
      (libsource (lib "") (part "TMC2226-SA-T"))
    )
    (comp (ref "U12")
      (value "TMC2226-SA-T")
      (fields (field (name "BOM_Supplier Part") "C705366"))
      (libsource (lib "") (part "TMC2226-SA-T"))
    )
    (comp (ref "U13")
      (value "TMC2226-SA-T")
      (fields (field (name "BOM_Supplier Part") "C705366"))
      (libsource (lib "") (part "TMC2226-SA-T"))
    )
    (comp (ref "U14")
      (value "TMC2226-SA-T")
      (fields (field (name "BOM_Supplier Part") "C705366"))
      (libsource (lib "") (part "TMC2226-SA-T"))
    )
    (comp (ref "U15")
      (value "TMC2226-SA-T")
      (fields (field (name "BOM_Supplier Part") "C705366"))
      (libsource (lib "") (part "TMC2226-SA-T"))
    )
    (comp (ref "U17")
      (value "470uF")
      (fields
        (field (name "BOM_Manufacturer Part") "25V470uF CD110")
        (field (name "BOM_Supplier Part") "C2960234")
      )
      (libsource (lib "") (part "25V470UF CD110_1"))
    )
    (comp (ref "U18")
      (value "74HCT595PW,112")
      (fields (field (name "BOM_Supplier Part") "C547810"))
      (libsource (lib "") (part "74HCT595PW,112"))
    )
    (comp (ref "U20")
      (value "470uF")
      (fields
        (field (name "BOM_Manufacturer Part") "25V470uF CD110")
        (field (name "BOM_Supplier Part") "C2960234")
      )
      (libsource (lib "") (part "25V470UF CD110"))
    )
    (comp (ref "U21")
      (value "AMS1117-3.3V")
      (fields (field (name "BOM_Supplier Part") "C2688239"))
      (libsource (lib "") (part "AMS1117-3.3V"))
    )
    (comp (ref "U22")
      (value "XL1509-5.0E1")
      (fields (field (name "BOM_Supplier Part") "C61063"))
      (libsource (lib "") (part "XL1509-5.0E1"))
    )
    (comp (ref "X0")
      (value "XH-4A")
      (fields (field (name "BOM_Supplier Part") "C37815"))
      (libsource (lib "") (part "XH-4A_1"))
    )
    (comp (ref "X_MIN")
      (value "XH-2A")
      (fields (field (name "BOM_Supplier Part") "C20079"))
      (libsource (lib "") (part "XH-2A_3"))
    )
    (comp (ref "Y0")
      (value "XH-4A")
      (fields (field (name "BOM_Supplier Part") "C37815"))
      (libsource (lib "") (part "XH-4A_2"))
    )
    (comp (ref "Y_MIN")
      (value "XH-2A")
      (fields (field (name "BOM_Supplier Part") "C20079"))
      (libsource (lib "") (part "XH-2A_1"))
    )
    (comp (ref "Z-PROBE")
      (value "XH-3A")
      (fields (field (name "BOM_Supplier Part") "C2316"))
      (libsource (lib "") (part "XH-3A"))
    )
    (comp (ref "Z-VCC")
      (value "DW254R-11-03-85")
      (fields (field (name "BOM_Supplier Part") "C2935897"))
      (libsource (lib "") (part "DW254R-11-03-85_1"))
    )
    (comp (ref "Z0")
      (value "XH-4A")
      (fields (field (name "BOM_Supplier Part") "C37815"))
      (libsource (lib "") (part "XH-4A"))
    )
    (comp (ref "Z1")
      (value "XH-4A")
      (fields (field (name "BOM_Supplier Part") "C37815"))
      (libsource (lib "") (part "XH-4A"))
    )
    (comp (ref "Z1_MIN")
      (value "XH-2A")
      (fields (field (name "BOM_Supplier Part") "C20079"))
      (libsource (lib "") (part "XH-2A_9"))
    )
    (comp (ref "Z2")
      (value "XH-4A")
      (fields (field (name "BOM_Supplier Part") "C37815"))
      (libsource (lib "") (part "XH-4A"))
    )
    (comp (ref "Z2_MIN")
      (value "XH-2A")
      (fields (field (name "BOM_Supplier Part") "C20079"))
      (libsource (lib "") (part "XH-2A_5"))
    )
    (comp (ref "Z3")
      (value "XH-4A")
      (fields (field (name "BOM_Supplier Part") "C37815"))
      (libsource (lib "") (part "XH-4A"))
    )
    (comp (ref "Z3_MIN")
      (value "XH-2A")
      (fields (field (name "BOM_Supplier Part") "C20079"))
      (libsource (lib "") (part "XH-2A_8"))
    )
  )
  (nets
    (net (code "1") (name "+3.3V") (class "Default")
      (node (ref "C11") (pin "2") (pinfunction "2_2") (pintype "unspecified"))
      (node (ref "C12") (pin "2") (pinfunction "2_2") (pintype "unspecified"))
      (node (ref "C20") (pin "2") (pinfunction "2_2") (pintype "unspecified"))
      (node (ref "C22") (pin "2") (pinfunction "2_2") (pintype "input"))
      (node (ref "C24") (pin "1") (pinfunction "1_1") (pintype "unspecified"))
      (node (ref "C32") (pin "1") (pinfunction "1_1") (pintype "unspecified"))
      (node (ref "C39") (pin "1") (pinfunction "1_1") (pintype "unspecified"))
      (node (ref "C50") (pin "1") (pinfunction "1_1") (pintype "unspecified"))
      (node (ref "C51") (pin "1") (pinfunction "1_1") (pintype "unspecified"))
      (node (ref "C70") (pin "1") (pinfunction "1_1") (pintype "unspecified"))
      (node (ref "C8") (pin "1") (pinfunction "1_1") (pintype "unspecified"))
      (node (ref "C85") (pin "2") (pinfunction "2_2") (pintype "unspecified"))
      (node (ref "C9") (pin "1") (pinfunction "1_1") (pintype "unspecified"))
      (node (ref "H1") (pin "1") (pinfunction "1_1") (pintype "input"))
      (node (ref "H1") (pin "2") (pinfunction "2_2") (pintype "input"))
      (node (ref "H2") (pin "1") (pinfunction "1_1") (pintype "input"))
      (node (ref "H2") (pin "2") (pinfunction "2_2") (pintype "input"))
      (node (ref "H3") (pin "1") (pinfunction "1_1") (pintype "input"))
      (node (ref "H3") (pin "2") (pinfunction "2_2") (pintype "input"))
      (node (ref "H4") (pin "1") (pinfunction "1_1") (pintype "input"))
      (node (ref "H4") (pin "2") (pinfunction "2_2") (pintype "input"))
      (node (ref "H5") (pin "1") (pinfunction "1_1") (pintype "input"))
      (node (ref "H5") (pin "2") (pinfunction "2_2") (pintype "input"))
      (node (ref "H6") (pin "1") (pinfunction "1_1") (pintype "input"))
      (node (ref "H6") (pin "2") (pinfunction "2_2") (pintype "input"))
      (node (ref "H7") (pin "1") (pinfunction "1_1") (pintype "input"))
      (node (ref "H7") (pin "2") (pinfunction "2_2") (pintype "input"))
      (node (ref "H8") (pin "1") (pinfunction "1_1") (pintype "input"))
      (node (ref "H8") (pin "2") (pinfunction "2_2") (pintype "input"))
      (node (ref "J1") (pin "4") (pinfunction "VDD_4") (pintype "input"))
      (node (ref "R12") (pin "2") (pinfunction "2_2") (pintype "unspecified"))
      (node (ref "R15") (pin "2") (pinfunction "2_2") (pintype "input"))
      (node (ref "R18") (pin "1") (pinfunction "1_1") (pintype "input"))
      (node (ref "R2") (pin "2") (pinfunction "2_2") (pintype "input"))
      (node (ref "R23") (pin "1") (pinfunction "1_1") (pintype "input"))
      (node (ref "R27") (pin "2") (pinfunction "2_2") (pintype "input"))
      (node (ref "R3") (pin "2") (pinfunction "2_2") (pintype "unspecified"))
      (node (ref "R45") (pin "1") (pinfunction "1_1") (pintype "input"))
      (node (ref "R48") (pin "1") (pinfunction "1_1") (pintype "input"))
      (node (ref "R52") (pin "1") (pinfunction "1_1") (pintype "input"))
      (node (ref "R_SD2") (pin "1") (pinfunction "1_1") (pintype "input"))
      (node (ref "R_SD3") (pin "1") (pinfunction "1_1") (pintype "input"))
      (node (ref "R_SD4") (pin "1") (pinfunction "1_1") (pintype "input"))
      (node (ref "R_SD5") (pin "1") (pinfunction "1_1") (pintype "input"))
      (node (ref "U11") (pin "19") (pinfunction "VCC_IO_19") (pintype "unspecified"))
      (node (ref "U12") (pin "19") (pinfunction "VCC_IO_19") (pintype "unspecified"))
      (node (ref "U13") (pin "19") (pinfunction "VCC_IO_19") (pintype "unspecified"))
      (node (ref "U14") (pin "19") (pinfunction "VCC_IO_19") (pintype "unspecified"))
      (node (ref "U15") (pin "19") (pinfunction "VCC_IO_19") (pintype "unspecified"))
      (node (ref "U2") (pin "19") (pinfunction "VCC_IO_19") (pintype "unspecified"))
      (node (ref "U21") (pin "2") (pinfunction "VOUT_2") (pintype "unspecified"))
      (node (ref "U21") (pin "4") (pinfunction "VOUT_4") (pintype "unspecified"))
      (node (ref "U3") (pin "2") (pinfunction "3V3_2") (pintype "unspecified"))
      (node (ref "U5") (pin "16") (pinfunction "VCC_16") (pintype "unspecified"))
      (node (ref "U8") (pin "19") (pinfunction "VCC_IO_19") (pintype "unspecified"))
      (node (ref "U9") (pin "19") (pinfunction "VCC_IO_19") (pintype "unspecified"))
    )
    (net (code "2") (name "+5V") (class "Default")
      (node (ref "C77") (pin "2") (pinfunction "2_2") (pintype "unspecified"))
      (node (ref "D1") (pin "1") (pinfunction "K_1") (pintype "unspecified"))
      (node (ref "FAN-VCC") (pin "1") (pinfunction "1_1") (pintype "unspecified"))
      (node (ref "L1") (pin "2") (pinfunction "2_2") (pintype "unspecified"))
      (node (ref "LCD1") (pin "1") (pinfunction "1_1") (pintype "input"))
      (node (ref "M-UART") (pin "1") (pinfunction "1_1") (pintype "unspecified"))
      (node (ref "M-UART") (pin "2") (pinfunction "2_2") (pintype "unspecified"))
      (node (ref "P13") (pin "1") (pinfunction "1_1") (pintype "unspecified"))
      (node (ref "U18") (pin "10") (pinfunction "MR#_10") (pintype "unspecified"))
      (node (ref "U18") (pin "16") (pinfunction "VCC_16") (pintype "unspecified"))
      (node (ref "U20") (pin "1") (pinfunction "1_1") (pintype "unspecified"))
      (node (ref "U21") (pin "3") (pinfunction "VIN_3") (pintype "unspecified"))
      (node (ref "U22") (pin "3") (pinfunction "FB_3") (pintype "unspecified"))
      (node (ref "U4") (pin "10") (pinfunction "MR#_10") (pintype "unspecified"))
      (node (ref "U4") (pin "16") (pinfunction "VCC_16") (pintype "unspecified"))
      (node (ref "U6") (pin "10") (pinfunction "MR#_10") (pintype "unspecified"))
      (node (ref "U6") (pin "16") (pinfunction "VCC_16") (pintype "unspecified"))
      (node (ref "U7") (pin "10") (pinfunction "MR#_10") (pintype "unspecified"))
      (node (ref "U7") (pin "16") (pinfunction "VCC_16") (pintype "unspecified"))
      (node (ref "Z-VCC") (pin "1") (pinfunction "1_1") (pintype "unspecified"))
    )
    (net (code "3") (name "+24V") (class "Default")
      (node (ref "24VIN") (pin "1") (pinfunction "1_1") (pintype "unspecified"))
      (node (ref "F1") (pin "1") (pinfunction "1_1") (pintype "unspecified"))
      (node (ref "F2") (pin "1") (pinfunction "1_1") (pintype "unspecified"))
    )
    (net (code "4") (name "24V2") (class "Default")
      (node (ref "24V") (pin "10") (pinfunction "10_10") (pintype "input"))
      (node (ref "24V") (pin "2") (pinfunction "2_2") (pintype "input"))
      (node (ref "24V") (pin "4") (pinfunction "4_4") (pintype "input"))
      (node (ref "24V") (pin "6") (pinfunction "6_6") (pintype "input"))
      (node (ref "24V") (pin "8") (pinfunction "8_8") (pintype "input"))
      (node (ref "C1") (pin "1") (pinfunction "1_1") (pintype "unspecified"))
      (node (ref "C19") (pin "2") (pinfunction "2_2") (pintype "unspecified"))
      (node (ref "C2") (pin "2") (pinfunction "2_2") (pintype "unspecified"))
      (node (ref "C28") (pin "1") (pinfunction "1_1") (pintype "input"))
      (node (ref "C29") (pin "2") (pinfunction "2_2") (pintype "unspecified"))
      (node (ref "C3") (pin "2") (pinfunction "2_2") (pintype "unspecified"))
      (node (ref "C30") (pin "2") (pinfunction "2_2") (pintype "unspecified"))
      (node (ref "C31") (pin "1") (pinfunction "1_1") (pintype "unspecified"))
      (node (ref "C35") (pin "1") (pinfunction "1_1") (pintype "input"))
      (node (ref "C36") (pin "2") (pinfunction "2_2") (pintype "unspecified"))
      (node (ref "C37") (pin "2") (pinfunction "2_2") (pintype "unspecified"))
      (node (ref "C38") (pin "1") (pinfunction "1_1") (pintype "unspecified"))
      (node (ref "C4") (pin "1") (pinfunction "1_1") (pintype "input"))
      (node (ref "C42") (pin "1") (pinfunction "1_1") (pintype "input"))
      (node (ref "C43") (pin "2") (pinfunction "2_2") (pintype "unspecified"))
      (node (ref "C44") (pin "1") (pinfunction "1_1") (pintype "unspecified"))
      (node (ref "C45") (pin "2") (pinfunction "2_2") (pintype "unspecified"))
      (node (ref "C46") (pin "2") (pinfunction "2_2") (pintype "unspecified"))
      (node (ref "C47") (pin "1") (pinfunction "1_1") (pintype "input"))
      (node (ref "C54") (pin "2") (pinfunction "2_2") (pintype "unspecified"))
      (node (ref "C55") (pin "1") (pinfunction "1_1") (pintype "input"))
      (node (ref "C56") (pin "2") (pinfunction "2_2") (pintype "unspecified"))
      (node (ref "C57") (pin "2") (pinfunction "2_2") (pintype "unspecified"))
      (node (ref "C58") (pin "1") (pinfunction "1_1") (pintype "unspecified"))
      (node (ref "C59") (pin "1") (pinfunction "1_1") (pintype "unspecified"))
      (node (ref "C60") (pin "1") (pinfunction "1_1") (pintype "input"))
      (node (ref "C61") (pin "2") (pinfunction "2_2") (pintype "unspecified"))
      (node (ref "C62") (pin "2") (pinfunction "2_2") (pintype "unspecified"))
      (node (ref "C63") (pin "1") (pinfunction "1_1") (pintype "unspecified"))
      (node (ref "C64") (pin "1") (pinfunction "1_1") (pintype "unspecified"))
      (node (ref "C65") (pin "2") (pinfunction "2_2") (pintype "unspecified"))
      (node (ref "C66") (pin "2") (pinfunction "2_2") (pintype "unspecified"))
      (node (ref "C67") (pin "1") (pinfunction "1_1") (pintype "input"))
      (node (ref "D6") (pin "1") (pinfunction "+_1") (pintype "unspecified"))
      (node (ref "D7") (pin "1") (pinfunction "K_1") (pintype "unspecified"))
      (node (ref "D8") (pin "1") (pinfunction "+_1") (pintype "unspecified"))
      (node (ref "D9") (pin "1") (pinfunction "K_1") (pintype "unspecified"))
      (node (ref "F1") (pin "2") (pinfunction "2_2") (pintype "unspecified"))
      (node (ref "F2") (pin "2") (pinfunction "2_2") (pintype "unspecified"))
      (node (ref "FAN-VCC") (pin "3") (pinfunction "3_3") (pintype "unspecified"))
      (node (ref "HB") (pin "1") (pinfunction "1_1") (pintype "unspecified"))
      (node (ref "HE0") (pin "1") (pinfunction "1_1") (pintype "unspecified"))
      (node (ref "U11") (pin "26") (pinfunction "VS_26") (pintype "unspecified"))
      (node (ref "U11") (pin "3") (pinfunction "VS_3") (pintype "unspecified"))
      (node (ref "U12") (pin "26") (pinfunction "VS_26") (pintype "unspecified"))
      (node (ref "U12") (pin "3") (pinfunction "VS_3") (pintype "unspecified"))
      (node (ref "U13") (pin "26") (pinfunction "VS_26") (pintype "unspecified"))
      (node (ref "U13") (pin "3") (pinfunction "VS_3") (pintype "unspecified"))
      (node (ref "U14") (pin "26") (pinfunction "VS_26") (pintype "unspecified"))
      (node (ref "U14") (pin "3") (pinfunction "VS_3") (pintype "unspecified"))
      (node (ref "U15") (pin "26") (pinfunction "VS_26") (pintype "unspecified"))
      (node (ref "U15") (pin "3") (pinfunction "VS_3") (pintype "unspecified"))
      (node (ref "U17") (pin "1") (pinfunction "1_1") (pintype "unspecified"))
      (node (ref "U2") (pin "26") (pinfunction "VS_26") (pintype "unspecified"))
      (node (ref "U2") (pin "3") (pinfunction "VS_3") (pintype "unspecified"))
      (node (ref "U22") (pin "1") (pinfunction "VIN_1") (pintype "unspecified"))
      (node (ref "U8") (pin "26") (pinfunction "VS_26") (pintype "unspecified"))
      (node (ref "U8") (pin "3") (pinfunction "VS_3") (pintype "unspecified"))
      (node (ref "U9") (pin "26") (pinfunction "VS_26") (pintype "unspecified"))
      (node (ref "U9") (pin "3") (pinfunction "VS_3") (pintype "unspecified"))
      (node (ref "Z-VCC") (pin "3") (pinfunction "3_3") (pintype "unspecified"))
    )
    (net (code "5") (name "BEEPER_PIN") (class "Default")
      (node (ref "LCD1") (pin "10") (pinfunction "10_10") (pintype "input"))
      (node (ref "U7") (pin "15") (pinfunction "Q0_15") (pintype "unspecified"))
    )
    (net (code "6") (name "BTN1") (class "Default")
      (node (ref "LCD2") (pin "8") (pinfunction "8_8") (pintype "input"))
      (node (ref "U3") (pin "16") (pinfunction "IO13_16") (pintype "unspecified"))
    )
    (net (code "7") (name "BTN2") (class "Default")
      (node (ref "LCD2") (pin "6") (pinfunction "6_6") (pintype "input"))
      (node (ref "U3") (pin "14") (pinfunction "IO12_14") (pintype "unspecified"))
    )
    (net (code "8") (name "BTNC") (class "Default")
      (node (ref "LCD1") (pin "9") (pinfunction "9_9") (pintype "input"))
      (node (ref "U3") (pin "13") (pinfunction "IO14_13") (pintype "unspecified"))
    )
    (net (code "9") (name "D+") (class "Default")
      (node (ref "C25") (pin "1") (pinfunction "1_1") (pintype "unspecified"))
      (node (ref "R36") (pin "1") (pinfunction "1_1") (pintype "unspecified"))
      (node (ref "U5") (pin "5") (pinfunction "D+_5") (pintype "unspecified"))
    )
    (net (code "10") (name "D-") (class "Default")
      (node (ref "C23") (pin "1") (pinfunction "1_1") (pintype "unspecified"))
      (node (ref "R37") (pin "1") (pinfunction "1_1") (pintype "unspecified"))
      (node (ref "U5") (pin "6") (pinfunction "D-_6") (pintype "unspecified"))
    )
    (net (code "11") (name "DTR") (class "Default")
      (node (ref "R5") (pin "2") (pinfunction "2_2") (pintype "input"))
      (node (ref "T2") (pin "2") (pinfunction "E_2") (pintype "input"))
      (node (ref "U5") (pin "13") (pinfunction "DTR#_13") (pintype "unspecified"))
    )
    (net (code "12") (name "E0-DIAG") (class "Default")
      (node (ref "H9") (pin "13") (pinfunction "13_13") (pintype "input"))
      (node (ref "U14") (pin "15") (pinfunction "DIAG_15") (pintype "unspecified"))
    )
    (net (code "13") (name "E0.DIR") (class "Default")
      (node (ref "U14") (pin "23") (pinfunction "DIR_23") (pintype "unspecified"))
      (node (ref "U4") (pin "5") (pinfunction "Q5_5") (pintype "unspecified"))
    )
    (net (code "14") (name "E0.EN") (class "Default")
      (node (ref "U14") (pin "5") (pinfunction "ENN_5") (pintype "unspecified"))
      (node (ref "U4") (pin "7") (pinfunction "Q7_7") (pintype "unspecified"))
    )
    (net (code "15") (name "E0.MS1") (class "Default")
      (node (ref "H8") (pin "3") (pinfunction "3_3") (pintype "input"))
      (node (ref "U14") (pin "12") (pinfunction "MS1_AD0_12") (pintype "unspecified"))
    )
    (net (code "16") (name "E0.MS2") (class "Default")
      (node (ref "H8") (pin "4") (pinfunction "4_4") (pintype "input"))
      (node (ref "U14") (pin "14") (pinfunction "MS2_AD1_14") (pintype "unspecified"))
    )
    (net (code "17") (name "E0.STP") (class "Default")
      (node (ref "U14") (pin "20") (pinfunction "STEP_20") (pintype "unspecified"))
      (node (ref "U4") (pin "6") (pinfunction "Q6_6") (pintype "unspecified"))
    )
    (net (code "18") (name "E1-DIAG") (class "Default")
      (node (ref "H9") (pin "15") (pinfunction "15_15") (pintype "input"))
      (node (ref "U12") (pin "15") (pinfunction "DIAG_15") (pintype "unspecified"))
    )
    (net (code "19") (name "E1.DIR") (class "Default")
      (node (ref "U12") (pin "23") (pinfunction "DIR_23") (pintype "unspecified"))
      (node (ref "U7") (pin "5") (pinfunction "Q5_5") (pintype "unspecified"))
    )
    (net (code "20") (name "E1.EN") (class "Default")
      (node (ref "U12") (pin "5") (pinfunction "ENN_5") (pintype "unspecified"))
      (node (ref "U7") (pin "7") (pinfunction "Q7_7") (pintype "unspecified"))
    )
    (net (code "21") (name "E1.MS1") (class "Default")
      (node (ref "H7") (pin "3") (pinfunction "3_3") (pintype "input"))
      (node (ref "U12") (pin "12") (pinfunction "MS1_AD0_12") (pintype "unspecified"))
    )
    (net (code "22") (name "E1.MS2") (class "Default")
      (node (ref "H7") (pin "4") (pinfunction "4_4") (pintype "input"))
      (node (ref "U12") (pin "14") (pinfunction "MS2_AD1_14") (pintype "unspecified"))
    )
    (net (code "23") (name "E1.STP") (class "Default")
      (node (ref "U12") (pin "20") (pinfunction "STEP_20") (pintype "unspecified"))
      (node (ref "U7") (pin "6") (pinfunction "Q6_6") (pintype "unspecified"))
    )
    (net (code "24") (name "EN") (class "Default")
      (node (ref "C13") (pin "1") (pinfunction "1_1") (pintype "unspecified"))
      (node (ref "LCD2") (pin "3") (pinfunction "3_3") (pintype "input"))
      (node (ref "R15") (pin "1") (pinfunction "1_1") (pintype "input"))
      (node (ref "R68") (pin "1") (pinfunction "1_1") (pintype "unspecified"))
      (node (ref "T1") (pin "3") (pinfunction "C_3") (pintype "input"))
      (node (ref "U3") (pin "3") (pinfunction "EN_3") (pintype "unspecified"))
    )
    (net (code "25") (name "FAN-VCC") (class "Default")
      (node (ref "D2") (pin "1") (pinfunction "+_1") (pintype "unspecified"))
      (node (ref "D4") (pin "1") (pinfunction "+_1") (pintype "unspecified"))
      (node (ref "FAN-VCC") (pin "2") (pinfunction "2_2") (pintype "unspecified"))
      (node (ref "FE0") (pin "1") (pinfunction "1_1") (pintype "unspecified"))
      (node (ref "FE1") (pin "1") (pinfunction "1_1") (pintype "unspecified"))
    )
    (net (code "26") (name "FAN_E0") (class "Default")
      (node (ref "R10") (pin "1") (pinfunction "1_1") (pintype "unspecified"))
      (node (ref "R11") (pin "2") (pinfunction "2_2") (pintype "unspecified"))
      (node (ref "U6") (pin "15") (pinfunction "Q0_15") (pintype "unspecified"))
    )
    (net (code "27") (name "FAN_E1") (class "Default")
      (node (ref "R49") (pin "2") (pinfunction "2_2") (pintype "unspecified"))
      (node (ref "R50") (pin "1") (pinfunction "1_1") (pintype "unspecified"))
      (node (ref "U7") (pin "1") (pinfunction "Q1_1") (pintype "unspecified"))
    )
    (net (code "28") (name "GND") (class "Default")
      (node (ref "24V") (pin "1") (pinfunction "1_1") (pintype "input"))
      (node (ref "24V") (pin "3") (pinfunction "3_3") (pintype "input"))
      (node (ref "24V") (pin "5") (pinfunction "5_5") (pintype "input"))
      (node (ref "24V") (pin "7") (pinfunction "7_7") (pintype "input"))
      (node (ref "24V") (pin "9") (pinfunction "9_9") (pintype "input"))
      (node (ref "24VIN") (pin "2") (pinfunction "2_2") (pintype "unspecified"))
      (node (ref "C10") (pin "1") (pinfunction "1_1") (pintype "unspecified"))
      (node (ref "C11") (pin "1") (pinfunction "1_1") (pintype "unspecified"))
      (node (ref "C12") (pin "1") (pinfunction "1_1") (pintype "unspecified"))
      (node (ref "C13") (pin "2") (pinfunction "2_2") (pintype "unspecified"))
      (node (ref "C14") (pin "1") (pinfunction "1_1") (pintype "unspecified"))
      (node (ref "C15") (pin "2") (pinfunction "2_2") (pintype "input"))
      (node (ref "C17") (pin "1") (pinfunction "1_1") (pintype "unspecified"))
      (node (ref "C18") (pin "1") (pinfunction "1_1") (pintype "unspecified"))
      (node (ref "C19") (pin "1") (pinfunction "1_1") (pintype "unspecified"))
      (node (ref "C2") (pin "1") (pinfunction "1_1") (pintype "unspecified"))
      (node (ref "C20") (pin "1") (pinfunction "1_1") (pintype "unspecified"))
      (node (ref "C21") (pin "1") (pinfunction "1_1") (pintype "input"))
      (node (ref "C22") (pin "1") (pinfunction "1_1") (pintype "input"))
      (node (ref "C23") (pin "2") (pinfunction "2_2") (pintype "unspecified"))
      (node (ref "C24") (pin "2") (pinfunction "2_2") (pintype "unspecified"))
      (node (ref "C25") (pin "2") (pinfunction "2_2") (pintype "unspecified"))
      (node (ref "C26") (pin "2") (pinfunction "2_2") (pintype "input"))
      (node (ref "C28") (pin "2") (pinfunction "2_2") (pintype "input"))
      (node (ref "C29") (pin "1") (pinfunction "1_1") (pintype "unspecified"))
      (node (ref "C3") (pin "1") (pinfunction "1_1") (pintype "unspecified"))
      (node (ref "C30") (pin "1") (pinfunction "1_1") (pintype "unspecified"))
      (node (ref "C32") (pin "2") (pinfunction "2_2") (pintype "unspecified"))
      (node (ref "C33") (pin "2") (pinfunction "2_2") (pintype "input"))
      (node (ref "C35") (pin "2") (pinfunction "2_2") (pintype "input"))
      (node (ref "C36") (pin "1") (pinfunction "1_1") (pintype "unspecified"))
      (node (ref "C37") (pin "1") (pinfunction "1_1") (pintype "unspecified"))
      (node (ref "C39") (pin "2") (pinfunction "2_2") (pintype "unspecified"))
      (node (ref "C4") (pin "2") (pinfunction "2_2") (pintype "input"))
      (node (ref "C40") (pin "2") (pinfunction "2_2") (pintype "input"))
      (node (ref "C42") (pin "2") (pinfunction "2_2") (pintype "input"))
      (node (ref "C43") (pin "1") (pinfunction "1_1") (pintype "unspecified"))
      (node (ref "C45") (pin "1") (pinfunction "1_1") (pintype "unspecified"))
      (node (ref "C46") (pin "1") (pinfunction "1_1") (pintype "unspecified"))
      (node (ref "C47") (pin "2") (pinfunction "2_2") (pintype "input"))
      (node (ref "C49") (pin "2") (pinfunction "2_2") (pintype "input"))
      (node (ref "C50") (pin "2") (pinfunction "2_2") (pintype "unspecified"))
      (node (ref "C51") (pin "2") (pinfunction "2_2") (pintype "unspecified"))
      (node (ref "C52") (pin "2") (pinfunction "2_2") (pintype "input"))
      (node (ref "C54") (pin "1") (pinfunction "1_1") (pintype "unspecified"))
      (node (ref "C55") (pin "2") (pinfunction "2_2") (pintype "input"))
      (node (ref "C56") (pin "1") (pinfunction "1_1") (pintype "unspecified"))
      (node (ref "C57") (pin "1") (pinfunction "1_1") (pintype "unspecified"))
      (node (ref "C6") (pin "2") (pinfunction "2_2") (pintype "input"))
      (node (ref "C60") (pin "2") (pinfunction "2_2") (pintype "input"))
      (node (ref "C61") (pin "1") (pinfunction "1_1") (pintype "unspecified"))
      (node (ref "C62") (pin "1") (pinfunction "1_1") (pintype "unspecified"))
      (node (ref "C65") (pin "1") (pinfunction "1_1") (pintype "unspecified"))
      (node (ref "C66") (pin "1") (pinfunction "1_1") (pintype "unspecified"))
      (node (ref "C67") (pin "2") (pinfunction "2_2") (pintype "input"))
      (node (ref "C69") (pin "2") (pinfunction "2_2") (pintype "input"))
      (node (ref "C7") (pin "1") (pinfunction "1_1") (pintype "unspecified"))
      (node (ref "C70") (pin "2") (pinfunction "2_2") (pintype "unspecified"))
      (node (ref "C75") (pin "1") (pinfunction "1_1") (pintype "unspecified"))
      (node (ref "C76") (pin "1") (pinfunction "1_1") (pintype "unspecified"))
      (node (ref "C77") (pin "1") (pinfunction "1_1") (pintype "unspecified"))
      (node (ref "C78") (pin "1") (pinfunction "1_1") (pintype "unspecified"))
      (node (ref "C8") (pin "2") (pinfunction "2_2") (pintype "unspecified"))
      (node (ref "C81") (pin "2") (pinfunction "2_2") (pintype "unspecified"))
      (node (ref "C82") (pin "2") (pinfunction "2_2") (pintype "unspecified"))
      (node (ref "C85") (pin "1") (pinfunction "1_1") (pintype "unspecified"))
      (node (ref "C9") (pin "2") (pinfunction "2_2") (pintype "unspecified"))
      (node (ref "D10") (pin "2") (pinfunction "2_2") (pintype "unspecified"))
      (node (ref "EXT-RST") (pin "1") (pinfunction "1_1") (pintype "unspecified"))
      (node (ref "H1") (pin "5") (pinfunction "5_5") (pintype "input"))
      (node (ref "H1") (pin "6") (pinfunction "6_6") (pintype "input"))
      (node (ref "H2") (pin "5") (pinfunction "5_5") (pintype "input"))
      (node (ref "H2") (pin "6") (pinfunction "6_6") (pintype "input"))
      (node (ref "H3") (pin "5") (pinfunction "5_5") (pintype "input"))
      (node (ref "H3") (pin "6") (pinfunction "6_6") (pintype "input"))
      (node (ref "H4") (pin "5") (pinfunction "5_5") (pintype "input"))
      (node (ref "H4") (pin "6") (pinfunction "6_6") (pintype "input"))
      (node (ref "H5") (pin "5") (pinfunction "5_5") (pintype "input"))
      (node (ref "H5") (pin "6") (pinfunction "6_6") (pintype "input"))
      (node (ref "H6") (pin "5") (pinfunction "5_5") (pintype "input"))
      (node (ref "H6") (pin "6") (pinfunction "6_6") (pintype "input"))
      (node (ref "H7") (pin "5") (pinfunction "5_5") (pintype "input"))
      (node (ref "H7") (pin "6") (pinfunction "6_6") (pintype "input"))
      (node (ref "H8") (pin "5") (pinfunction "5_5") (pintype "input"))
      (node (ref "H8") (pin "6") (pinfunction "6_6") (pintype "input"))
      (node (ref "J1") (pin "10") (pinfunction "GND_10") (pintype "input"))
      (node (ref "J1") (pin "11") (pinfunction "GND_11") (pintype "input"))
      (node (ref "J1") (pin "12") (pinfunction "GND_12") (pintype "input"))
      (node (ref "J1") (pin "13") (pinfunction "GND_13") (pintype "input"))
      (node (ref "J1") (pin "6") (pinfunction "VSS_6") (pintype "input"))
      (node (ref "J2") (pin "13") (pinfunction "GND_13") (pintype "unspecified"))
      (node (ref "J2") (pin "14") (pinfunction "GND_14") (pintype "unspecified"))
      (node (ref "J2") (pin "15") (pinfunction "GND_15") (pintype "unspecified"))
      (node (ref "J2") (pin "16") (pinfunction "GND_16") (pintype "unspecified"))
      (node (ref "J2") (pin "A1B12") (pinfunction "GND_A1B12") (pintype "unspecified"))
      (node (ref "J2") (pin "B1A12") (pinfunction "GND_B1A12") (pintype "unspecified"))
      (node (ref "LCD1") (pin "2") (pinfunction "2_2") (pintype "input"))
      (node (ref "LCD2") (pin "2") (pinfunction "2_2") (pintype "input"))
      (node (ref "M-UART") (pin "3") (pinfunction "3_3") (pintype "unspecified"))
      (node (ref "M-UART") (pin "4") (pinfunction "4_4") (pintype "unspecified"))
      (node (ref "P13") (pin "2") (pinfunction "2_2") (pintype "unspecified"))
      (node (ref "Q1") (pin "2") (pinfunction "S_2") (pintype "unspecified"))
      (node (ref "Q2") (pin "3") (pinfunction "S_3") (pintype "unspecified"))
      (node (ref "Q3") (pin "3") (pinfunction "S_3") (pintype "unspecified"))
      (node (ref "Q4") (pin "2") (pinfunction "S_2") (pintype "unspecified"))
      (node (ref "R11") (pin "1") (pinfunction "1_1") (pintype "unspecified"))
      (node (ref "R14") (pin "2") (pinfunction "2_2") (pintype "unspecified"))
      (node (ref "R20") (pin "1") (pinfunction "1_1") (pintype "unspecified"))
      (node (ref "R21") (pin "1") (pinfunction "1_1") (pintype "unspecified"))
      (node (ref "R22") (pin "1") (pinfunction "1_1") (pintype "unspecified"))
      (node (ref "R28") (pin "1") (pinfunction "1_1") (pintype "unspecified"))
      (node (ref "R30") (pin "1") (pinfunction "1_1") (pintype "unspecified"))
      (node (ref "R31") (pin "2") (pinfunction "2_2") (pintype "unspecified"))
      (node (ref "R32") (pin "1") (pinfunction "1_1") (pintype "unspecified"))
      (node (ref "R33") (pin "2") (pinfunction "2_2") (pintype "unspecified"))
      (node (ref "R38") (pin "2") (pinfunction "2_2") (pintype "unspecified"))
      (node (ref "R39") (pin "2") (pinfunction "2_2") (pintype "unspecified"))
      (node (ref "R4") (pin "1") (pinfunction "1_1") (pintype "unspecified"))
      (node (ref "R40") (pin "1") (pinfunction "1_1") (pintype "unspecified"))
      (node (ref "R41") (pin "1") (pinfunction "1_1") (pintype "unspecified"))
      (node (ref "R42") (pin "1") (pinfunction "1_1") (pintype "unspecified"))
      (node (ref "R43") (pin "2") (pinfunction "2_2") (pintype "unspecified"))
      (node (ref "R49") (pin "1") (pinfunction "1_1") (pintype "unspecified"))
      (node (ref "R8") (pin "2") (pinfunction "2_2") (pintype "unspecified"))
      (node (ref "R9") (pin "2") (pinfunction "2_2") (pintype "unspecified"))
      (node (ref "SW1") (pin "3") (pinfunction "3_3") (pintype "unspecified"))
      (node (ref "SW1") (pin "4") (pinfunction "4_4") (pintype "unspecified"))
      (node (ref "TB") (pin "2") (pinfunction "2_2") (pintype "unspecified"))
      (node (ref "TE0") (pin "2") (pinfunction "2_2") (pintype "unspecified"))
      (node (ref "U1") (pin "2") (pinfunction "-_2") (pintype "unspecified"))
      (node (ref "U10") (pin "3") (pinfunction "3_3") (pintype "unspecified"))
      (node (ref "U11") (pin "22") (pinfunction "GND_22") (pintype "unspecified"))
      (node (ref "U11") (pin "6") (pinfunction "GND_6") (pintype "unspecified"))
      (node (ref "U12") (pin "22") (pinfunction "GND_22") (pintype "unspecified"))
      (node (ref "U12") (pin "6") (pinfunction "GND_6") (pintype "unspecified"))
      (node (ref "U13") (pin "22") (pinfunction "GND_22") (pintype "unspecified"))
      (node (ref "U13") (pin "6") (pinfunction "GND_6") (pintype "unspecified"))
      (node (ref "U14") (pin "22") (pinfunction "GND_22") (pintype "unspecified"))
      (node (ref "U14") (pin "6") (pinfunction "GND_6") (pintype "unspecified"))
      (node (ref "U15") (pin "22") (pinfunction "GND_22") (pintype "unspecified"))
      (node (ref "U15") (pin "6") (pinfunction "GND_6") (pintype "unspecified"))
      (node (ref "U17") (pin "2") (pinfunction "2_2") (pintype "unspecified"))
      (node (ref "U18") (pin "13") (pinfunction "OE#_13") (pintype "unspecified"))
      (node (ref "U18") (pin "8") (pinfunction "GND_8") (pintype "unspecified"))
      (node (ref "U2") (pin "22") (pinfunction "GND_22") (pintype "unspecified"))
      (node (ref "U2") (pin "6") (pinfunction "GND_6") (pintype "unspecified"))
      (node (ref "U20") (pin "2") (pinfunction "2_2") (pintype "unspecified"))
      (node (ref "U21") (pin "1") (pinfunction "ADJ/GND_1") (pintype "unspecified"))
      (node (ref "U22") (pin "4") (pinfunction "ON/OFF_4") (pintype "unspecified"))
      (node (ref "U22") (pin "5") (pinfunction "GND_5") (pintype "unspecified"))
      (node (ref "U22") (pin "6") (pinfunction "GND_6") (pintype "unspecified"))
      (node (ref "U22") (pin "7") (pinfunction "GND_7") (pintype "unspecified"))
      (node (ref "U22") (pin "8") (pinfunction "GND_8") (pintype "unspecified"))
      (node (ref "U3") (pin "1") (pinfunction "GND_1") (pintype "unspecified"))
      (node (ref "U3") (pin "15") (pinfunction "GND_15") (pintype "unspecified"))
      (node (ref "U3") (pin "38") (pinfunction "GND_38") (pintype "unspecified"))
      (node (ref "U4") (pin "13") (pinfunction "OE#_13") (pintype "unspecified"))
      (node (ref "U4") (pin "8") (pinfunction "GND_8") (pintype "unspecified"))
      (node (ref "U5") (pin "1") (pinfunction "GND_1") (pintype "unspecified"))
      (node (ref "U6") (pin "13") (pinfunction "OE#_13") (pintype "unspecified"))
      (node (ref "U6") (pin "8") (pinfunction "GND_8") (pintype "unspecified"))
      (node (ref "U7") (pin "13") (pinfunction "OE#_13") (pintype "unspecified"))
      (node (ref "U7") (pin "8") (pinfunction "GND_8") (pintype "unspecified"))
      (node (ref "U8") (pin "22") (pinfunction "GND_22") (pintype "unspecified"))
      (node (ref "U8") (pin "6") (pinfunction "GND_6") (pintype "unspecified"))
      (node (ref "U9") (pin "22") (pinfunction "GND_22") (pintype "unspecified"))
      (node (ref "U9") (pin "6") (pinfunction "GND_6") (pintype "unspecified"))
      (node (ref "X_MIN") (pin "2") (pinfunction "2_2") (pintype "unspecified"))
      (node (ref "Y_MIN") (pin "2") (pinfunction "2_2") (pintype "unspecified"))
      (node (ref "Z-PROBE") (pin "3") (pinfunction "3_3") (pintype "unspecified"))
      (node (ref "Z1_MIN") (pin "2") (pinfunction "2_2") (pintype "unspecified"))
      (node (ref "Z2_MIN") (pin "2") (pinfunction "2_2") (pintype "unspecified"))
      (node (ref "Z3_MIN") (pin "2") (pinfunction "2_2") (pintype "unspecified"))
    )
    (net (code "29") (name "Heater_BED") (class "Default")
      (node (ref "R17") (pin "1") (pinfunction "1_1") (pintype "unspecified"))
      (node (ref "R20") (pin "2") (pinfunction "2_2") (pintype "unspecified"))
      (node (ref "U18") (pin "15") (pinfunction "Q0_15") (pintype "unspecified"))
    )
    (net (code "30") (name "Heater_E0") (class "Default")
      (node (ref "R26") (pin "1") (pinfunction "1_1") (pintype "unspecified"))
      (node (ref "R28") (pin "2") (pinfunction "2_2") (pintype "unspecified"))
      (node (ref "U4") (pin "15") (pinfunction "Q0_15") (pintype "unspecified"))
    )
    (net (code "31") (name "I2S_BCK") (class "Default")
      (node (ref "U18") (pin "11") (pinfunction "SHCP_11") (pintype "unspecified"))
      (node (ref "U3") (pin "12") (pinfunction "IO27_12") (pintype "unspecified"))
      (node (ref "U4") (pin "11") (pinfunction "SHCP_11") (pintype "unspecified"))
      (node (ref "U6") (pin "11") (pinfunction "SHCP_11") (pintype "unspecified"))
      (node (ref "U7") (pin "11") (pinfunction "SHCP_11") (pintype "unspecified"))
    )
    (net (code "32") (name "I2S_DATA") (class "Default")
      (node (ref "U3") (pin "10") (pinfunction "IO25_10") (pintype "unspecified"))
      (node (ref "U4") (pin "14") (pinfunction "DS_14") (pintype "unspecified"))
    )
    (net (code "33") (name "I2S_WS") (class "Default")
      (node (ref "U18") (pin "12") (pinfunction "STCP_12") (pintype "unspecified"))
      (node (ref "U3") (pin "11") (pinfunction "IO26_11") (pintype "unspecified"))
      (node (ref "U4") (pin "12") (pinfunction "STCP_12") (pintype "unspecified"))
      (node (ref "U6") (pin "12") (pinfunction "STCP_12") (pintype "unspecified"))
      (node (ref "U7") (pin "12") (pinfunction "STCP_12") (pintype "unspecified"))
    )
    (net (code "34") (name "IO0") (class "Default")
      (node (ref "T2") (pin "3") (pinfunction "C_3") (pintype "input"))
      (node (ref "U3") (pin "25") (pinfunction "IO0_25") (pintype "unspecified"))
    )
    (net (code "35") (name "M-RX") (class "Default")
      (node (ref "M-UART") (pin "6") (pinfunction "6_6") (pintype "unspecified"))
      (node (ref "R1") (pin "1") (pinfunction "1_1") (pintype "input"))
      (node (ref "U11") (pin "18") (pinfunction "PDN_UART_18") (pintype "unspecified"))
      (node (ref "U12") (pin "18") (pinfunction "PDN_UART_18") (pintype "unspecified"))
      (node (ref "U13") (pin "18") (pinfunction "PDN_UART_18") (pintype "unspecified"))
      (node (ref "U14") (pin "18") (pinfunction "PDN_UART_18") (pintype "unspecified"))
    )
    (net (code "36") (name "M-TX") (class "Default")
      (node (ref "M-UART") (pin "8") (pinfunction "8_8") (pintype "unspecified"))
      (node (ref "R1") (pin "2") (pinfunction "2_2") (pintype "input"))
    )
    (net (code "37") (name "MISO") (class "Default")
      (node (ref "J1") (pin "7") (pinfunction "DAT0(D0)_7") (pintype "bidirectional"))
      (node (ref "LCD2") (pin "10") (pinfunction "10_10") (pintype "input"))
      (node (ref "R_SD2") (pin "2") (pinfunction "2_2") (pintype "input"))
      (node (ref "U3") (pin "31") (pinfunction "IO19_31") (pintype "unspecified"))
    )
    (net (code "38") (name "MOSI") (class "Default")
      (node (ref "J1") (pin "3") (pinfunction "CMD(DI)_3") (pintype "input"))
      (node (ref "LCD2") (pin "5") (pinfunction "5_5") (pintype "input"))
      (node (ref "R_SD4") (pin "2") (pinfunction "2_2") (pintype "input"))
      (node (ref "U3") (pin "37") (pinfunction "IO23_37") (pintype "unspecified"))
    )
    (net (code "39") (name "Net-(C18-Pad2)") (class "Default")
      (node (ref "C18") (pin "2") (pinfunction "2_2") (pintype "unspecified"))
      (node (ref "R27") (pin "1") (pinfunction "1_1") (pintype "input"))
      (node (ref "R29") (pin "2") (pinfunction "2_2") (pintype "unspecified"))
      (node (ref "U10") (pin "4") (pinfunction "4_4") (pintype "unspecified"))
    )
    (net (code "40") (name "Net-(D2--)") (class "Default")
      (node (ref "D2") (pin "2") (pinfunction "-_2") (pintype "unspecified"))
      (node (ref "R7") (pin "2") (pinfunction "2_2") (pintype "unspecified"))
    )
    (net (code "41") (name "Net-(D4--)") (class "Default")
      (node (ref "D4") (pin "2") (pinfunction "-_2") (pintype "unspecified"))
      (node (ref "R53") (pin "2") (pinfunction "2_2") (pintype "unspecified"))
    )
    (net (code "42") (name "Net-(D6--)") (class "Default")
      (node (ref "D6") (pin "2") (pinfunction "-_2") (pintype "unspecified"))
      (node (ref "R16") (pin "2") (pinfunction "2_2") (pintype "input"))
    )
    (net (code "43") (name "Net-(D7-A)") (class "Default")
      (node (ref "D7") (pin "2") (pinfunction "A_2") (pintype "unspecified"))
      (node (ref "HB") (pin "2") (pinfunction "2_2") (pintype "unspecified"))
      (node (ref "Q2") (pin "2") (pinfunction "D_2") (pintype "unspecified"))
      (node (ref "R16") (pin "1") (pinfunction "1_1") (pintype "input"))
    )
    (net (code "44") (name "Net-(D8--)") (class "Default")
      (node (ref "D8") (pin "2") (pinfunction "-_2") (pintype "unspecified"))
      (node (ref "R25") (pin "2") (pinfunction "2_2") (pintype "input"))
    )
    (net (code "45") (name "Net-(D9-A)") (class "Default")
      (node (ref "D9") (pin "2") (pinfunction "A_2") (pintype "unspecified"))
      (node (ref "HE0") (pin "2") (pinfunction "2_2") (pintype "unspecified"))
      (node (ref "Q3") (pin "2") (pinfunction "D_2") (pintype "unspecified"))
      (node (ref "R25") (pin "1") (pinfunction "1_1") (pintype "input"))
    )
    (net (code "46") (name "Net-(EXT-RST-Pad2)") (class "Default")
      (node (ref "EXT-RST") (pin "2") (pinfunction "2_2") (pintype "unspecified"))
      (node (ref "R68") (pin "2") (pinfunction "2_2") (pintype "unspecified"))
      (node (ref "SW1") (pin "1") (pinfunction "1_1") (pintype "unspecified"))
      (node (ref "SW1") (pin "2") (pinfunction "2_2") (pintype "unspecified"))
    )
    (net (code "47") (name "Net-(Q1-D)") (class "Default")
      (node (ref "FE0") (pin "2") (pinfunction "2_2") (pintype "unspecified"))
      (node (ref "Q1") (pin "3") (pinfunction "D_3") (pintype "unspecified"))
      (node (ref "R7") (pin "1") (pinfunction "1_1") (pintype "unspecified"))
    )
    (net (code "48") (name "Net-(Q1-G)") (class "Default")
      (node (ref "Q1") (pin "1") (pinfunction "G_1") (pintype "unspecified"))
      (node (ref "R10") (pin "2") (pinfunction "2_2") (pintype "unspecified"))
    )
    (net (code "49") (name "Net-(Q2-G)") (class "Default")
      (node (ref "Q2") (pin "1") (pinfunction "G_1") (pintype "unspecified"))
      (node (ref "R17") (pin "2") (pinfunction "2_2") (pintype "unspecified"))
    )
    (net (code "50") (name "Net-(Q3-G)") (class "Default")
      (node (ref "Q3") (pin "1") (pinfunction "G_1") (pintype "unspecified"))
      (node (ref "R26") (pin "2") (pinfunction "2_2") (pintype "unspecified"))
    )
    (net (code "51") (name "Net-(Q4-D)") (class "Default")
      (node (ref "FE1") (pin "2") (pinfunction "2_2") (pintype "unspecified"))
      (node (ref "Q4") (pin "3") (pinfunction "D_3") (pintype "unspecified"))
      (node (ref "R53") (pin "1") (pinfunction "1_1") (pintype "unspecified"))
    )
    (net (code "52") (name "Net-(Q4-G)") (class "Default")
      (node (ref "Q4") (pin "1") (pinfunction "G_1") (pintype "unspecified"))
      (node (ref "R50") (pin "2") (pinfunction "2_2") (pintype "unspecified"))
    )
    (net (code "53") (name "Net-(R13-Pad2)") (class "Default")
      (node (ref "R13") (pin "2") (pinfunction "2_2") (pintype "unspecified"))
      (node (ref "U10") (pin "1") (pinfunction "1_1") (pintype "unspecified"))
    )
    (net (code "54") (name "Net-(R19-Pad2)") (class "Default")
      (node (ref "R19") (pin "2") (pinfunction "2_2") (pintype "unspecified"))
      (node (ref "X_MIN") (pin "1") (pinfunction "1_1") (pintype "unspecified"))
    )
    (net (code "55") (name "Net-(R24-Pad2)") (class "Default")
      (node (ref "R24") (pin "2") (pinfunction "2_2") (pintype "unspecified"))
      (node (ref "Y_MIN") (pin "1") (pinfunction "1_1") (pintype "unspecified"))
    )
    (net (code "56") (name "Net-(R46-Pad2)") (class "Default")
      (node (ref "R46") (pin "2") (pinfunction "2_2") (pintype "unspecified"))
      (node (ref "Z2_MIN") (pin "1") (pinfunction "1_1") (pintype "unspecified"))
    )
    (net (code "57") (name "Net-(R47-Pad2)") (class "Default")
      (node (ref "R47") (pin "2") (pinfunction "2_2") (pintype "unspecified"))
      (node (ref "Z1_MIN") (pin "1") (pinfunction "1_1") (pintype "unspecified"))
    )
    (net (code "58") (name "Net-(R51-Pad2)") (class "Default")
      (node (ref "R51") (pin "2") (pinfunction "2_2") (pintype "unspecified"))
      (node (ref "Z3_MIN") (pin "1") (pinfunction "1_1") (pintype "unspecified"))
    )
    (net (code "59") (name "Net-(T1-B)") (class "Default")
      (node (ref "R5") (pin "1") (pinfunction "1_1") (pintype "input"))
      (node (ref "T1") (pin "1") (pinfunction "B_1") (pintype "input"))
    )
    (net (code "60") (name "Net-(T2-B)") (class "Default")
      (node (ref "R6") (pin "1") (pinfunction "1_1") (pintype "input"))
      (node (ref "T2") (pin "1") (pinfunction "B_1") (pintype "input"))
    )
    (net (code "61") (name "Net-(U1-+)") (class "Default")
      (node (ref "R2") (pin "1") (pinfunction "1_1") (pintype "input"))
      (node (ref "U1") (pin "1") (pinfunction "+_1") (pintype "unspecified"))
    )
    (net (code "62") (name "Net-(U2-5VOUT)") (class "Default")
      (node (ref "C6") (pin "1") (pinfunction "1_1") (pintype "input"))
      (node (ref "U2") (pin "11") (pinfunction "5VOUT_11") (pintype "unspecified"))
    )
    (net (code "63") (name "Net-(U2-BRA)") (class "Default")
      (node (ref "R4") (pin "2") (pinfunction "2_2") (pintype "unspecified"))
      (node (ref "U2") (pin "27") (pinfunction "BRA_27") (pintype "unspecified"))
    )
    (net (code "64") (name "Net-(U2-BRB)") (class "Default")
      (node (ref "R8") (pin "1") (pinfunction "1_1") (pintype "unspecified"))
      (node (ref "U2") (pin "2") (pinfunction "BRB_2") (pintype "unspecified"))
    )
    (net (code "65") (name "Net-(U2-CPI)") (class "Default")
      (node (ref "C5") (pin "2") (pinfunction "2_2") (pintype "unspecified"))
      (node (ref "U2") (pin "8") (pinfunction "CPI_8") (pintype "unspecified"))
    )
    (net (code "66") (name "Net-(U2-CPO)") (class "Default")
      (node (ref "C5") (pin "1") (pinfunction "1_1") (pintype "unspecified"))
      (node (ref "U2") (pin "7") (pinfunction "CPO_7") (pintype "unspecified"))
    )
    (net (code "67") (name "Net-(U2-OA1)") (class "Default")
      (node (ref "U2") (pin "28") (pinfunction "OA1_28") (pintype "unspecified"))
      (node (ref "Z0") (pin "3") (pinfunction "3_3") (pintype "unspecified"))
    )
    (net (code "68") (name "Net-(U2-OA2)") (class "Default")
      (node (ref "U2") (pin "25") (pinfunction "OA2_25") (pintype "unspecified"))
      (node (ref "Z0") (pin "4") (pinfunction "4_4") (pintype "unspecified"))
    )
    (net (code "69") (name "Net-(U2-OB1)") (class "Default")
      (node (ref "U2") (pin "1") (pinfunction "OB1_1") (pintype "unspecified"))
      (node (ref "Z0") (pin "2") (pinfunction "2_2") (pintype "unspecified"))
    )
    (net (code "70") (name "Net-(U2-OB2)") (class "Default")
      (node (ref "U2") (pin "4") (pinfunction "OB2_4") (pintype "unspecified"))
      (node (ref "Z0") (pin "1") (pinfunction "1_1") (pintype "unspecified"))
    )
    (net (code "71") (name "Net-(U2-VCP)") (class "Default")
      (node (ref "C1") (pin "2") (pinfunction "2_2") (pintype "unspecified"))
      (node (ref "U2") (pin "9") (pinfunction "VCP_9") (pintype "unspecified"))
    )
    (net (code "72") (name "Net-(U5-RXD)") (class "Default")
      (node (ref "R34") (pin "2") (pinfunction "2_2") (pintype "input"))
      (node (ref "U5") (pin "3") (pinfunction "RXD_3") (pintype "unspecified"))
    )
    (net (code "73") (name "Net-(U5-TXD)") (class "Default")
      (node (ref "R35") (pin "2") (pinfunction "2_2") (pintype "input"))
      (node (ref "U5") (pin "2") (pinfunction "TXD_2") (pintype "unspecified"))
    )
    (net (code "74") (name "Net-(U5-V3)") (class "Default")
      (node (ref "C21") (pin "2") (pinfunction "2_2") (pintype "input"))
      (node (ref "U5") (pin "4") (pinfunction "V3_4") (pintype "unspecified"))
    )
    (net (code "75") (name "Net-(U6-Q7S)") (class "Default")
      (node (ref "U6") (pin "9") (pinfunction "Q7S_9") (pintype "unspecified"))
      (node (ref "U7") (pin "14") (pinfunction "DS_14") (pintype "unspecified"))
    )
    (net (code "76") (name "Net-(U8-5VOUT)") (class "Default")
      (node (ref "C26") (pin "1") (pinfunction "1_1") (pintype "input"))
      (node (ref "U8") (pin "11") (pinfunction "5VOUT_11") (pintype "unspecified"))
    )
    (net (code "77") (name "Net-(U8-BRA)") (class "Default")
      (node (ref "R21") (pin "2") (pinfunction "2_2") (pintype "unspecified"))
      (node (ref "U8") (pin "27") (pinfunction "BRA_27") (pintype "unspecified"))
    )
    (net (code "78") (name "Net-(U8-BRB)") (class "Default")
      (node (ref "R14") (pin "1") (pinfunction "1_1") (pintype "unspecified"))
      (node (ref "U8") (pin "2") (pinfunction "BRB_2") (pintype "unspecified"))
    )
    (net (code "79") (name "Net-(U8-CPI)") (class "Default")
      (node (ref "C27") (pin "2") (pinfunction "2_2") (pintype "unspecified"))
      (node (ref "U8") (pin "8") (pinfunction "CPI_8") (pintype "unspecified"))
    )
    (net (code "80") (name "Net-(U8-CPO)") (class "Default")
      (node (ref "C27") (pin "1") (pinfunction "1_1") (pintype "unspecified"))
      (node (ref "U8") (pin "7") (pinfunction "CPO_7") (pintype "unspecified"))
    )
    (net (code "81") (name "Net-(U8-OA1)") (class "Default")
      (node (ref "U8") (pin "28") (pinfunction "OA1_28") (pintype "unspecified"))
      (node (ref "Z2") (pin "3") (pinfunction "3_3") (pintype "unspecified"))
    )
    (net (code "82") (name "Net-(U8-OA2)") (class "Default")
      (node (ref "U8") (pin "25") (pinfunction "OA2_25") (pintype "unspecified"))
      (node (ref "Z2") (pin "4") (pinfunction "4_4") (pintype "unspecified"))
    )
    (net (code "83") (name "Net-(U8-OB1)") (class "Default")
      (node (ref "U8") (pin "1") (pinfunction "OB1_1") (pintype "unspecified"))
      (node (ref "Z2") (pin "2") (pinfunction "2_2") (pintype "unspecified"))
    )
    (net (code "84") (name "Net-(U8-OB2)") (class "Default")
      (node (ref "U8") (pin "4") (pinfunction "OB2_4") (pintype "unspecified"))
      (node (ref "Z2") (pin "1") (pinfunction "1_1") (pintype "unspecified"))
    )
    (net (code "85") (name "Net-(U8-VCP)") (class "Default")
      (node (ref "C31") (pin "2") (pinfunction "2_2") (pintype "unspecified"))
      (node (ref "U8") (pin "9") (pinfunction "VCP_9") (pintype "unspecified"))
    )
    (net (code "86") (name "Net-(U9-5VOUT)") (class "Default")
      (node (ref "C33") (pin "1") (pinfunction "1_1") (pintype "input"))
      (node (ref "U9") (pin "11") (pinfunction "5VOUT_11") (pintype "unspecified"))
    )
    (net (code "87") (name "Net-(U9-BRA)") (class "Default")
      (node (ref "R32") (pin "2") (pinfunction "2_2") (pintype "unspecified"))
      (node (ref "U9") (pin "27") (pinfunction "BRA_27") (pintype "unspecified"))
    )
    (net (code "88") (name "Net-(U9-BRB)") (class "Default")
      (node (ref "R31") (pin "1") (pinfunction "1_1") (pintype "unspecified"))
      (node (ref "U9") (pin "2") (pinfunction "BRB_2") (pintype "unspecified"))
    )
    (net (code "89") (name "Net-(U9-CPI)") (class "Default")
      (node (ref "C34") (pin "2") (pinfunction "2_2") (pintype "unspecified"))
      (node (ref "U9") (pin "8") (pinfunction "CPI_8") (pintype "unspecified"))
    )
    (net (code "90") (name "Net-(U9-CPO)") (class "Default")
      (node (ref "C34") (pin "1") (pinfunction "1_1") (pintype "unspecified"))
      (node (ref "U9") (pin "7") (pinfunction "CPO_7") (pintype "unspecified"))
    )
    (net (code "91") (name "Net-(U9-OA1)") (class "Default")
      (node (ref "U9") (pin "28") (pinfunction "OA1_28") (pintype "unspecified"))
      (node (ref "Z3") (pin "3") (pinfunction "3_3") (pintype "unspecified"))
    )
    (net (code "92") (name "Net-(U9-OA2)") (class "Default")
      (node (ref "U9") (pin "25") (pinfunction "OA2_25") (pintype "unspecified"))
      (node (ref "Z3") (pin "4") (pinfunction "4_4") (pintype "unspecified"))
    )
    (net (code "93") (name "Net-(U9-OB1)") (class "Default")
      (node (ref "U9") (pin "1") (pinfunction "OB1_1") (pintype "unspecified"))
      (node (ref "Z3") (pin "2") (pinfunction "2_2") (pintype "unspecified"))
    )
    (net (code "94") (name "Net-(U9-OB2)") (class "Default")
      (node (ref "U9") (pin "4") (pinfunction "OB2_4") (pintype "unspecified"))
      (node (ref "Z3") (pin "1") (pinfunction "1_1") (pintype "unspecified"))
    )
    (net (code "95") (name "Net-(U9-VCP)") (class "Default")
      (node (ref "C38") (pin "2") (pinfunction "2_2") (pintype "unspecified"))
      (node (ref "U9") (pin "9") (pinfunction "VCP_9") (pintype "unspecified"))
    )
    (net (code "96") (name "Net-(U10-Pad2)") (class "Default")
      (node (ref "U10") (pin "2") (pinfunction "2_2") (pintype "unspecified"))
      (node (ref "Z-PROBE") (pin "2") (pinfunction "2_2") (pintype "unspecified"))
    )
    (net (code "97") (name "Net-(U11-5VOUT)") (class "Default")
      (node (ref "C49") (pin "1") (pinfunction "1_1") (pintype "input"))
      (node (ref "U11") (pin "11") (pinfunction "5VOUT_11") (pintype "unspecified"))
    )
    (net (code "98") (name "Net-(U11-BRA)") (class "Default")
      (node (ref "R22") (pin "2") (pinfunction "2_2") (pintype "unspecified"))
      (node (ref "U11") (pin "27") (pinfunction "BRA_27") (pintype "unspecified"))
    )
    (net (code "99") (name "Net-(U11-BRB)") (class "Default")
      (node (ref "R38") (pin "1") (pinfunction "1_1") (pintype "unspecified"))
      (node (ref "U11") (pin "2") (pinfunction "BRB_2") (pintype "unspecified"))
    )
    (net (code "100") (name "Net-(U11-CPI)") (class "Default")
      (node (ref "C48") (pin "2") (pinfunction "2_2") (pintype "unspecified"))
      (node (ref "U11") (pin "8") (pinfunction "CPI_8") (pintype "unspecified"))
    )
    (net (code "101") (name "Net-(U11-CPO)") (class "Default")
      (node (ref "C48") (pin "1") (pinfunction "1_1") (pintype "unspecified"))
      (node (ref "U11") (pin "7") (pinfunction "CPO_7") (pintype "unspecified"))
    )
    (net (code "102") (name "Net-(U11-OA1)") (class "Default")
      (node (ref "U11") (pin "28") (pinfunction "OA1_28") (pintype "unspecified"))
      (node (ref "Y0") (pin "3") (pinfunction "3_3") (pintype "unspecified"))
    )
    (net (code "103") (name "Net-(U11-OA2)") (class "Default")
      (node (ref "U11") (pin "25") (pinfunction "OA2_25") (pintype "unspecified"))
      (node (ref "Y0") (pin "4") (pinfunction "4_4") (pintype "unspecified"))
    )
    (net (code "104") (name "Net-(U11-OB1)") (class "Default")
      (node (ref "U11") (pin "1") (pinfunction "OB1_1") (pintype "unspecified"))
      (node (ref "Y0") (pin "2") (pinfunction "2_2") (pintype "unspecified"))
    )
    (net (code "105") (name "Net-(U11-OB2)") (class "Default")
      (node (ref "U11") (pin "4") (pinfunction "OB2_4") (pintype "unspecified"))
      (node (ref "Y0") (pin "1") (pinfunction "1_1") (pintype "unspecified"))
    )
    (net (code "106") (name "Net-(U11-VCP)") (class "Default")
      (node (ref "C44") (pin "2") (pinfunction "2_2") (pintype "unspecified"))
      (node (ref "U11") (pin "9") (pinfunction "VCP_9") (pintype "unspecified"))
    )
    (net (code "107") (name "Net-(U12-5VOUT)") (class "Default")
      (node (ref "C52") (pin "1") (pinfunction "1_1") (pintype "input"))
      (node (ref "U12") (pin "11") (pinfunction "5VOUT_11") (pintype "unspecified"))
    )
    (net (code "108") (name "Net-(U12-BRA)") (class "Default")
      (node (ref "R40") (pin "2") (pinfunction "2_2") (pintype "unspecified"))
      (node (ref "U12") (pin "27") (pinfunction "BRA_27") (pintype "unspecified"))
    )
    (net (code "109") (name "Net-(U12-BRB)") (class "Default")
      (node (ref "R39") (pin "1") (pinfunction "1_1") (pintype "unspecified"))
      (node (ref "U12") (pin "2") (pinfunction "BRB_2") (pintype "unspecified"))
    )
    (net (code "110") (name "Net-(U12-CPI)") (class "Default")
      (node (ref "C53") (pin "2") (pinfunction "2_2") (pintype "unspecified"))
      (node (ref "U12") (pin "8") (pinfunction "CPI_8") (pintype "unspecified"))
    )
    (net (code "111") (name "Net-(U12-CPO)") (class "Default")
      (node (ref "C53") (pin "1") (pinfunction "1_1") (pintype "unspecified"))
      (node (ref "U12") (pin "7") (pinfunction "CPO_7") (pintype "unspecified"))
    )
    (net (code "112") (name "Net-(U12-OA1)") (class "Default")
      (node (ref "E1") (pin "3") (pinfunction "3_3") (pintype "unspecified"))
      (node (ref "U12") (pin "28") (pinfunction "OA1_28") (pintype "unspecified"))
    )
    (net (code "113") (name "Net-(U12-OA2)") (class "Default")
      (node (ref "E1") (pin "4") (pinfunction "4_4") (pintype "unspecified"))
      (node (ref "U12") (pin "25") (pinfunction "OA2_25") (pintype "unspecified"))
    )
    (net (code "114") (name "Net-(U12-OB1)") (class "Default")
      (node (ref "E1") (pin "2") (pinfunction "2_2") (pintype "unspecified"))
      (node (ref "U12") (pin "1") (pinfunction "OB1_1") (pintype "unspecified"))
    )
    (net (code "115") (name "Net-(U12-OB2)") (class "Default")
      (node (ref "E1") (pin "1") (pinfunction "1_1") (pintype "unspecified"))
      (node (ref "U12") (pin "4") (pinfunction "OB2_4") (pintype "unspecified"))
    )
    (net (code "116") (name "Net-(U12-VCP)") (class "Default")
      (node (ref "C59") (pin "2") (pinfunction "2_2") (pintype "unspecified"))
      (node (ref "U12") (pin "9") (pinfunction "VCP_9") (pintype "unspecified"))
    )
    (net (code "117") (name "Net-(U13-5VOUT)") (class "Default")
      (node (ref "C40") (pin "1") (pinfunction "1_1") (pintype "input"))
      (node (ref "U13") (pin "11") (pinfunction "5VOUT_11") (pintype "unspecified"))
    )
    (net (code "118") (name "Net-(U13-BRA)") (class "Default")
      (node (ref "R41") (pin "2") (pinfunction "2_2") (pintype "unspecified"))
      (node (ref "U13") (pin "27") (pinfunction "BRA_27") (pintype "unspecified"))
    )
    (net (code "119") (name "Net-(U13-BRB)") (class "Default")
      (node (ref "R33") (pin "1") (pinfunction "1_1") (pintype "unspecified"))
      (node (ref "U13") (pin "2") (pinfunction "BRB_2") (pintype "unspecified"))
    )
    (net (code "120") (name "Net-(U13-CPI)") (class "Default")
      (node (ref "C41") (pin "2") (pinfunction "2_2") (pintype "unspecified"))
      (node (ref "U13") (pin "8") (pinfunction "CPI_8") (pintype "unspecified"))
    )
    (net (code "121") (name "Net-(U13-CPO)") (class "Default")
      (node (ref "C41") (pin "1") (pinfunction "1_1") (pintype "unspecified"))
      (node (ref "U13") (pin "7") (pinfunction "CPO_7") (pintype "unspecified"))
    )
    (net (code "122") (name "Net-(U13-OA1)") (class "Default")
      (node (ref "U13") (pin "28") (pinfunction "OA1_28") (pintype "unspecified"))
      (node (ref "X0") (pin "3") (pinfunction "3_3") (pintype "unspecified"))
    )
    (net (code "123") (name "Net-(U13-OA2)") (class "Default")
      (node (ref "U13") (pin "25") (pinfunction "OA2_25") (pintype "unspecified"))
      (node (ref "X0") (pin "4") (pinfunction "4_4") (pintype "unspecified"))
    )
    (net (code "124") (name "Net-(U13-OB1)") (class "Default")
      (node (ref "U13") (pin "1") (pinfunction "OB1_1") (pintype "unspecified"))
      (node (ref "X0") (pin "2") (pinfunction "2_2") (pintype "unspecified"))
    )
    (net (code "125") (name "Net-(U13-OB2)") (class "Default")
      (node (ref "U13") (pin "4") (pinfunction "OB2_4") (pintype "unspecified"))
      (node (ref "X0") (pin "1") (pinfunction "1_1") (pintype "unspecified"))
    )
    (net (code "126") (name "Net-(U13-VCP)") (class "Default")
      (node (ref "C63") (pin "2") (pinfunction "2_2") (pintype "unspecified"))
      (node (ref "U13") (pin "9") (pinfunction "VCP_9") (pintype "unspecified"))
    )
    (net (code "127") (name "Net-(U14-5VOUT)") (class "Default")
      (node (ref "C69") (pin "1") (pinfunction "1_1") (pintype "input"))
      (node (ref "U14") (pin "11") (pinfunction "5VOUT_11") (pintype "unspecified"))
    )
    (net (code "128") (name "Net-(U14-BRA)") (class "Default")
      (node (ref "R42") (pin "2") (pinfunction "2_2") (pintype "unspecified"))
      (node (ref "U14") (pin "27") (pinfunction "BRA_27") (pintype "unspecified"))
    )
    (net (code "129") (name "Net-(U14-BRB)") (class "Default")
      (node (ref "R43") (pin "1") (pinfunction "1_1") (pintype "unspecified"))
      (node (ref "U14") (pin "2") (pinfunction "BRB_2") (pintype "unspecified"))
    )
    (net (code "130") (name "Net-(U14-CPI)") (class "Default")
      (node (ref "C68") (pin "2") (pinfunction "2_2") (pintype "unspecified"))
      (node (ref "U14") (pin "8") (pinfunction "CPI_8") (pintype "unspecified"))
    )
    (net (code "131") (name "Net-(U14-CPO)") (class "Default")
      (node (ref "C68") (pin "1") (pinfunction "1_1") (pintype "unspecified"))
      (node (ref "U14") (pin "7") (pinfunction "CPO_7") (pintype "unspecified"))
    )
    (net (code "132") (name "Net-(U14-OA1)") (class "Default")
      (node (ref "E0") (pin "3") (pinfunction "3_3") (pintype "unspecified"))
      (node (ref "U14") (pin "28") (pinfunction "OA1_28") (pintype "unspecified"))
    )
    (net (code "133") (name "Net-(U14-OA2)") (class "Default")
      (node (ref "E0") (pin "4") (pinfunction "4_4") (pintype "unspecified"))
      (node (ref "U14") (pin "25") (pinfunction "OA2_25") (pintype "unspecified"))
    )
    (net (code "134") (name "Net-(U14-OB1)") (class "Default")
      (node (ref "E0") (pin "2") (pinfunction "2_2") (pintype "unspecified"))
      (node (ref "U14") (pin "1") (pinfunction "OB1_1") (pintype "unspecified"))
    )
    (net (code "135") (name "Net-(U14-OB2)") (class "Default")
      (node (ref "E0") (pin "1") (pinfunction "1_1") (pintype "unspecified"))
      (node (ref "U14") (pin "4") (pinfunction "OB2_4") (pintype "unspecified"))
    )
    (net (code "136") (name "Net-(U14-VCP)") (class "Default")
      (node (ref "C64") (pin "2") (pinfunction "2_2") (pintype "unspecified"))
      (node (ref "U14") (pin "9") (pinfunction "VCP_9") (pintype "unspecified"))
    )
    (net (code "137") (name "Net-(U15-5VOUT)") (class "Default")
      (node (ref "C15") (pin "1") (pinfunction "1_1") (pintype "input"))
      (node (ref "U15") (pin "11") (pinfunction "5VOUT_11") (pintype "unspecified"))
    )
    (net (code "138") (name "Net-(U15-BRA)") (class "Default")
      (node (ref "R30") (pin "2") (pinfunction "2_2") (pintype "unspecified"))
      (node (ref "U15") (pin "27") (pinfunction "BRA_27") (pintype "unspecified"))
    )
    (net (code "139") (name "Net-(U15-BRB)") (class "Default")
      (node (ref "R9") (pin "1") (pinfunction "1_1") (pintype "unspecified"))
      (node (ref "U15") (pin "2") (pinfunction "BRB_2") (pintype "unspecified"))
    )
    (net (code "140") (name "Net-(U15-CPI)") (class "Default")
      (node (ref "C16") (pin "2") (pinfunction "2_2") (pintype "unspecified"))
      (node (ref "U15") (pin "8") (pinfunction "CPI_8") (pintype "unspecified"))
    )
    (net (code "141") (name "Net-(U15-CPO)") (class "Default")
      (node (ref "C16") (pin "1") (pinfunction "1_1") (pintype "unspecified"))
      (node (ref "U15") (pin "7") (pinfunction "CPO_7") (pintype "unspecified"))
    )
    (net (code "142") (name "Net-(U15-OA1)") (class "Default")
      (node (ref "U15") (pin "28") (pinfunction "OA1_28") (pintype "unspecified"))
      (node (ref "Z1") (pin "3") (pinfunction "3_3") (pintype "unspecified"))
    )
    (net (code "143") (name "Net-(U15-OA2)") (class "Default")
      (node (ref "U15") (pin "25") (pinfunction "OA2_25") (pintype "unspecified"))
      (node (ref "Z1") (pin "4") (pinfunction "4_4") (pintype "unspecified"))
    )
    (net (code "144") (name "Net-(U15-OB1)") (class "Default")
      (node (ref "U15") (pin "1") (pinfunction "OB1_1") (pintype "unspecified"))
      (node (ref "Z1") (pin "2") (pinfunction "2_2") (pintype "unspecified"))
    )
    (net (code "145") (name "Net-(U15-OB2)") (class "Default")
      (node (ref "U15") (pin "4") (pinfunction "OB2_4") (pintype "unspecified"))
      (node (ref "Z1") (pin "1") (pinfunction "1_1") (pintype "unspecified"))
    )
    (net (code "146") (name "Net-(U15-VCP)") (class "Default")
      (node (ref "C58") (pin "2") (pinfunction "2_2") (pintype "unspecified"))
      (node (ref "U15") (pin "9") (pinfunction "VCP_9") (pintype "unspecified"))
    )
    (net (code "147") (name "Net-(U18-DS)") (class "Default")
      (node (ref "U18") (pin "14") (pinfunction "DS_14") (pintype "unspecified"))
      (node (ref "U4") (pin "9") (pinfunction "Q7S_9") (pintype "unspecified"))
    )
    (net (code "148") (name "Net-(U18-Q7S)") (class "Default")
      (node (ref "U18") (pin "9") (pinfunction "Q7S_9") (pintype "unspecified"))
      (node (ref "U6") (pin "14") (pinfunction "DS_14") (pintype "unspecified"))
    )
    (net (code "149") (name "Net-(U22-OUTPUT)") (class "Default")
      (node (ref "D10") (pin "1") (pinfunction "1_1") (pintype "unspecified"))
      (node (ref "L1") (pin "1") (pinfunction "1_1") (pintype "unspecified"))
      (node (ref "U22") (pin "2") (pinfunction "OUTPUT_2") (pintype "unspecified"))
    )
    (net (code "150") (name "RTS") (class "Default")
      (node (ref "R6") (pin "2") (pinfunction "2_2") (pintype "input"))
      (node (ref "T1") (pin "2") (pinfunction "E_2") (pintype "input"))
      (node (ref "U5") (pin "14") (pinfunction "RTS#_14") (pintype "unspecified"))
    )
    (net (code "151") (name "RXD0") (class "Default")
      (node (ref "P13") (pin "3") (pinfunction "3_3") (pintype "unspecified"))
      (node (ref "R35") (pin "1") (pinfunction "1_1") (pintype "input"))
      (node (ref "U3") (pin "34") (pinfunction "RXD0_34") (pintype "unspecified"))
    )
    (net (code "152") (name "RXD1") (class "Default")
      (node (ref "M-UART") (pin "5") (pinfunction "5_5") (pintype "unspecified"))
      (node (ref "U3") (pin "27") (pinfunction "IO16_27") (pintype "unspecified"))
    )
    (net (code "153") (name "SCK") (class "Default")
      (node (ref "J1") (pin "5") (pinfunction "CLK(SCLK)_5") (pintype "input"))
      (node (ref "LCD2") (pin "9") (pinfunction "9_9") (pintype "input"))
      (node (ref "R_SD5") (pin "2") (pinfunction "2_2") (pintype "input"))
      (node (ref "U3") (pin "30") (pinfunction "IO18_30") (pintype "unspecified"))
    )
    (net (code "154") (name "SCREEN-SCL") (class "Default")
      (node (ref "LCD2") (pin "1") (pinfunction "1_1") (pintype "input"))
      (node (ref "U3") (pin "36") (pinfunction "IO22_36") (pintype "unspecified"))
    )
    (net (code "155") (name "SCREEN-SDA") (class "Default")
      (node (ref "LCD2") (pin "4") (pinfunction "4_4") (pintype "input"))
      (node (ref "U3") (pin "33") (pinfunction "IO21_33") (pintype "unspecified"))
    )
    (net (code "156") (name "SS") (class "Default")
      (node (ref "J1") (pin "2") (pinfunction "CDDAT3(CS)_2") (pintype "bidirectional"))
      (node (ref "LCD2") (pin "7") (pinfunction "7_7") (pintype "input"))
      (node (ref "R_SD3") (pin "2") (pinfunction "2_2") (pintype "input"))
      (node (ref "U3") (pin "29") (pinfunction "IO5_29") (pintype "unspecified"))
    )
    (net (code "157") (name "TB") (class "Default")
      (node (ref "C10") (pin "2") (pinfunction "2_2") (pintype "unspecified"))
      (node (ref "R12") (pin "1") (pinfunction "1_1") (pintype "unspecified"))
      (node (ref "TB") (pin "1") (pinfunction "1_1") (pintype "unspecified"))
      (node (ref "U3") (pin "5") (pinfunction "SENSOR_VN_5") (pintype "unspecified"))
    )
    (net (code "158") (name "TE") (class "Default")
      (node (ref "C7") (pin "2") (pinfunction "2_2") (pintype "unspecified"))
      (node (ref "R3") (pin "1") (pinfunction "1_1") (pintype "unspecified"))
      (node (ref "TE0") (pin "1") (pinfunction "1_1") (pintype "unspecified"))
      (node (ref "U3") (pin "4") (pinfunction "SENSOR_VP_4") (pintype "unspecified"))
    )
    (net (code "159") (name "TXD0") (class "Default")
      (node (ref "P13") (pin "4") (pinfunction "4_4") (pintype "unspecified"))
      (node (ref "R34") (pin "1") (pinfunction "1_1") (pintype "input"))
      (node (ref "U3") (pin "35") (pinfunction "TXD0_35") (pintype "unspecified"))
    )
    (net (code "160") (name "TXD1") (class "Default")
      (node (ref "M-UART") (pin "7") (pinfunction "7_7") (pintype "unspecified"))
      (node (ref "U3") (pin "28") (pinfunction "IO17_28") (pintype "unspecified"))
    )
    (net (code "161") (name "UD+") (class "Default")
      (node (ref "J2") (pin "A6") (pinfunction "DP1_A6") (pintype "unspecified"))
      (node (ref "J2") (pin "B6") (pinfunction "DP2_B6") (pintype "unspecified"))
      (node (ref "R36") (pin "2") (pinfunction "2_2") (pintype "unspecified"))
    )
    (net (code "162") (name "UD-") (class "Default")
      (node (ref "J2") (pin "A7") (pinfunction "DN1_A7") (pintype "unspecified"))
      (node (ref "J2") (pin "B7") (pinfunction "DN2_B7") (pintype "unspecified"))
      (node (ref "R37") (pin "2") (pinfunction "2_2") (pintype "unspecified"))
    )
    (net (code "163") (name "UVCC") (class "Default")
      (node (ref "C81") (pin "1") (pinfunction "1_1") (pintype "unspecified"))
      (node (ref "C82") (pin "1") (pinfunction "1_1") (pintype "unspecified"))
      (node (ref "D1") (pin "2") (pinfunction "A_2") (pintype "unspecified"))
      (node (ref "J2") (pin "A4B9") (pinfunction "VBUS_A4B9") (pintype "unspecified"))
      (node (ref "J2") (pin "B4A9") (pinfunction "VBUS_B4A9") (pintype "unspecified"))
    )
    (net (code "164") (name "X0-DIAG") (class "Default")
      (node (ref "H9") (pin "1") (pinfunction "1_1") (pintype "input"))
      (node (ref "U13") (pin "15") (pinfunction "DIAG_15") (pintype "unspecified"))
    )
    (net (code "165") (name "X0.DIR") (class "Default")
      (node (ref "U13") (pin "23") (pinfunction "DIR_23") (pintype "unspecified"))
      (node (ref "U4") (pin "2") (pinfunction "Q2_2") (pintype "unspecified"))
    )
    (net (code "166") (name "X0.EN") (class "Default")
      (node (ref "U13") (pin "5") (pinfunction "ENN_5") (pintype "unspecified"))
      (node (ref "U4") (pin "4") (pinfunction "Q4_4") (pintype "unspecified"))
    )
    (net (code "167") (name "X0.MS1") (class "Default")
      (node (ref "H5") (pin "3") (pinfunction "3_3") (pintype "input"))
      (node (ref "U13") (pin "12") (pinfunction "MS1_AD0_12") (pintype "unspecified"))
    )
    (net (code "168") (name "X0.MS2") (class "Default")
      (node (ref "H5") (pin "4") (pinfunction "4_4") (pintype "input"))
      (node (ref "U13") (pin "14") (pinfunction "MS2_AD1_14") (pintype "unspecified"))
    )
    (net (code "169") (name "X0.STP") (class "Default")
      (node (ref "U13") (pin "20") (pinfunction "STEP_20") (pintype "unspecified"))
      (node (ref "U4") (pin "3") (pinfunction "Q3_3") (pintype "unspecified"))
    )
    (net (code "170") (name "X0_MIN") (class "Default")
      (node (ref "C14") (pin "2") (pinfunction "2_2") (pintype "unspecified"))
      (node (ref "H9") (pin "2") (pinfunction "2_2") (pintype "input"))
      (node (ref "R18") (pin "2") (pinfunction "2_2") (pintype "input"))
      (node (ref "R19") (pin "1") (pinfunction "1_1") (pintype "unspecified"))
      (node (ref "U3") (pin "6") (pinfunction "IO34_6") (pintype "unspecified"))
    )
    (net (code "171") (name "Y0-DIAG") (class "Default")
      (node (ref "H9") (pin "3") (pinfunction "3_3") (pintype "input"))
      (node (ref "U11") (pin "15") (pinfunction "DIAG_15") (pintype "unspecified"))
    )
    (net (code "172") (name "Y0.DIR") (class "Default")
      (node (ref "U11") (pin "23") (pinfunction "DIR_23") (pintype "unspecified"))
      (node (ref "U18") (pin "3") (pinfunction "Q3_3") (pintype "unspecified"))
    )
    (net (code "173") (name "Y0.EN") (class "Default")
      (node (ref "U11") (pin "5") (pinfunction "ENN_5") (pintype "unspecified"))
      (node (ref "U18") (pin "5") (pinfunction "Q5_5") (pintype "unspecified"))
    )
    (net (code "174") (name "Y0.MS1") (class "Default")
      (node (ref "H6") (pin "3") (pinfunction "3_3") (pintype "input"))
      (node (ref "U11") (pin "12") (pinfunction "MS1_AD0_12") (pintype "unspecified"))
    )
    (net (code "175") (name "Y0.MS2") (class "Default")
      (node (ref "H6") (pin "4") (pinfunction "4_4") (pintype "input"))
      (node (ref "U11") (pin "14") (pinfunction "MS2_AD1_14") (pintype "unspecified"))
    )
    (net (code "176") (name "Y0.STP") (class "Default")
      (node (ref "U11") (pin "20") (pinfunction "STEP_20") (pintype "unspecified"))
      (node (ref "U18") (pin "4") (pinfunction "Q4_4") (pintype "unspecified"))
    )
    (net (code "177") (name "Y0_MIN") (class "Default")
      (node (ref "C17") (pin "2") (pinfunction "2_2") (pintype "unspecified"))
      (node (ref "H9") (pin "4") (pinfunction "4_4") (pintype "input"))
      (node (ref "R23") (pin "2") (pinfunction "2_2") (pintype "input"))
      (node (ref "R24") (pin "1") (pinfunction "1_1") (pintype "unspecified"))
      (node (ref "U3") (pin "7") (pinfunction "IO35_7") (pintype "unspecified"))
    )
    (net (code "178") (name "Z-VCC") (class "Default")
      (node (ref "R13") (pin "1") (pinfunction "1_1") (pintype "unspecified"))
      (node (ref "Z-PROBE") (pin "1") (pinfunction "1_1") (pintype "unspecified"))
      (node (ref "Z-VCC") (pin "2") (pinfunction "2_2") (pintype "unspecified"))
    )
    (net (code "179") (name "Z0-DIAG") (class "Default")
      (node (ref "H9") (pin "5") (pinfunction "5_5") (pintype "input"))
      (node (ref "U2") (pin "15") (pinfunction "DIAG_15") (pintype "unspecified"))
    )
    (net (code "180") (name "Z0.DIR") (class "Default")
      (node (ref "U2") (pin "23") (pinfunction "DIR_23") (pintype "unspecified"))
      (node (ref "U6") (pin "4") (pinfunction "Q4_4") (pintype "unspecified"))
    )
    (net (code "181") (name "Z0.EN") (class "Default")
      (node (ref "U2") (pin "5") (pinfunction "ENN_5") (pintype "unspecified"))
      (node (ref "U6") (pin "6") (pinfunction "Q6_6") (pintype "unspecified"))
    )
    (net (code "182") (name "Z0.MS1") (class "Default")
      (node (ref "H1") (pin "3") (pinfunction "3_3") (pintype "input"))
      (node (ref "U2") (pin "12") (pinfunction "MS1_AD0_12") (pintype "unspecified"))
    )
    (net (code "183") (name "Z0.MS2") (class "Default")
      (node (ref "H1") (pin "4") (pinfunction "4_4") (pintype "input"))
      (node (ref "U2") (pin "14") (pinfunction "MS2_AD1_14") (pintype "unspecified"))
    )
    (net (code "184") (name "Z0.STP") (class "Default")
      (node (ref "U2") (pin "20") (pinfunction "STEP_20") (pintype "unspecified"))
      (node (ref "U6") (pin "5") (pinfunction "Q5_5") (pintype "unspecified"))
    )
    (net (code "185") (name "Z0_MIN") (class "Default")
      (node (ref "H9") (pin "6") (pinfunction "6_6") (pintype "input"))
      (node (ref "R29") (pin "1") (pinfunction "1_1") (pintype "unspecified"))
      (node (ref "U3") (pin "8") (pinfunction "IO32_8") (pintype "unspecified"))
    )
    (net (code "186") (name "Z1-DIAG") (class "Default")
      (node (ref "H9") (pin "7") (pinfunction "7_7") (pintype "input"))
      (node (ref "U15") (pin "15") (pinfunction "DIAG_15") (pintype "unspecified"))
    )
    (net (code "187") (name "Z1.DIR") (class "Default")
      (node (ref "U15") (pin "23") (pinfunction "DIR_23") (pintype "unspecified"))
      (node (ref "U18") (pin "6") (pinfunction "Q6_6") (pintype "unspecified"))
    )
    (net (code "188") (name "Z1.EN") (class "Default")
      (node (ref "U15") (pin "5") (pinfunction "ENN_5") (pintype "unspecified"))
      (node (ref "U4") (pin "1") (pinfunction "Q1_1") (pintype "unspecified"))
    )
    (net (code "189") (name "Z1.MS1") (class "Default")
      (node (ref "H2") (pin "3") (pinfunction "3_3") (pintype "input"))
      (node (ref "U15") (pin "12") (pinfunction "MS1_AD0_12") (pintype "unspecified"))
    )
    (net (code "190") (name "Z1.MS2") (class "Default")
      (node (ref "H2") (pin "4") (pinfunction "4_4") (pintype "input"))
      (node (ref "U15") (pin "14") (pinfunction "MS2_AD1_14") (pintype "unspecified"))
    )
    (net (code "191") (name "Z1.STP") (class "Default")
      (node (ref "U15") (pin "20") (pinfunction "STEP_20") (pintype "unspecified"))
      (node (ref "U18") (pin "7") (pinfunction "Q7_7") (pintype "unspecified"))
    )
    (net (code "192") (name "Z1_MIN") (class "Default")
      (node (ref "C76") (pin "2") (pinfunction "2_2") (pintype "unspecified"))
      (node (ref "H9") (pin "8") (pinfunction "8_8") (pintype "input"))
      (node (ref "R47") (pin "1") (pinfunction "1_1") (pintype "unspecified"))
      (node (ref "R48") (pin "2") (pinfunction "2_2") (pintype "input"))
      (node (ref "U3") (pin "9") (pinfunction "IO33_9") (pintype "unspecified"))
    )
    (net (code "193") (name "Z2-DIAG") (class "Default")
      (node (ref "H9") (pin "9") (pinfunction "9_9") (pintype "input"))
      (node (ref "U8") (pin "15") (pinfunction "DIAG_15") (pintype "unspecified"))
    )
    (net (code "194") (name "Z2.DIR") (class "Default")
      (node (ref "U6") (pin "7") (pinfunction "Q7_7") (pintype "unspecified"))
      (node (ref "U8") (pin "23") (pinfunction "DIR_23") (pintype "unspecified"))
    )
    (net (code "195") (name "Z2.EN") (class "Default")
      (node (ref "U18") (pin "2") (pinfunction "Q2_2") (pintype "unspecified"))
      (node (ref "U8") (pin "5") (pinfunction "ENN_5") (pintype "unspecified"))
    )
    (net (code "196") (name "Z2.MS1") (class "Default")
      (node (ref "H3") (pin "3") (pinfunction "3_3") (pintype "input"))
      (node (ref "U8") (pin "12") (pinfunction "MS1_AD0_12") (pintype "unspecified"))
    )
    (net (code "197") (name "Z2.MS2") (class "Default")
      (node (ref "H3") (pin "4") (pinfunction "4_4") (pintype "input"))
      (node (ref "U8") (pin "14") (pinfunction "MS2_AD1_14") (pintype "unspecified"))
    )
    (net (code "198") (name "Z2.STP") (class "Default")
      (node (ref "U18") (pin "1") (pinfunction "Q1_1") (pintype "unspecified"))
      (node (ref "U8") (pin "20") (pinfunction "STEP_20") (pintype "unspecified"))
    )
    (net (code "199") (name "Z2_MIN") (class "Default")
      (node (ref "C75") (pin "2") (pinfunction "2_2") (pintype "unspecified"))
      (node (ref "H9") (pin "10") (pinfunction "10_10") (pintype "input"))
      (node (ref "R45") (pin "2") (pinfunction "2_2") (pintype "input"))
      (node (ref "R46") (pin "1") (pinfunction "1_1") (pintype "unspecified"))
      (node (ref "U3") (pin "24") (pinfunction "IO2_24") (pintype "unspecified"))
    )
    (net (code "200") (name "Z3-DIAG") (class "Default")
      (node (ref "H9") (pin "11") (pinfunction "11_11") (pintype "input"))
      (node (ref "U9") (pin "15") (pinfunction "DIAG_15") (pintype "unspecified"))
    )
    (net (code "201") (name "Z3.DIR") (class "Default")
      (node (ref "U6") (pin "1") (pinfunction "Q1_1") (pintype "unspecified"))
      (node (ref "U9") (pin "23") (pinfunction "DIR_23") (pintype "unspecified"))
    )
    (net (code "202") (name "Z3.EN") (class "Default")
      (node (ref "U6") (pin "3") (pinfunction "Q3_3") (pintype "unspecified"))
      (node (ref "U9") (pin "5") (pinfunction "ENN_5") (pintype "unspecified"))
    )
    (net (code "203") (name "Z3.MS1") (class "Default")
      (node (ref "H4") (pin "3") (pinfunction "3_3") (pintype "input"))
      (node (ref "U9") (pin "12") (pinfunction "MS1_AD0_12") (pintype "unspecified"))
    )
    (net (code "204") (name "Z3.MS2") (class "Default")
      (node (ref "H4") (pin "4") (pinfunction "4_4") (pintype "input"))
      (node (ref "U9") (pin "14") (pinfunction "MS2_AD1_14") (pintype "unspecified"))
    )
    (net (code "205") (name "Z3.STP") (class "Default")
      (node (ref "U6") (pin "2") (pinfunction "Q2_2") (pintype "unspecified"))
      (node (ref "U9") (pin "20") (pinfunction "STEP_20") (pintype "unspecified"))
    )
    (net (code "206") (name "Z3_MIN") (class "Default")
      (node (ref "C78") (pin "2") (pinfunction "2_2") (pintype "unspecified"))
      (node (ref "H9") (pin "12") (pinfunction "12_12") (pintype "input"))
      (node (ref "R51") (pin "1") (pinfunction "1_1") (pintype "unspecified"))
      (node (ref "R52") (pin "2") (pinfunction "2_2") (pintype "input"))
      (node (ref "U3") (pin "23") (pinfunction "IO15_23") (pintype "unspecified"))
    )
    (net (code "207") (name "unconnected-(H9-Pad14)") (class "Default")
      (node (ref "H9") (pin "14") (pinfunction "14_14") (pintype "input+no_connect"))
    )
    (net (code "208") (name "unconnected-(H9-Pad16)") (class "Default")
      (node (ref "H9") (pin "16") (pinfunction "16_16") (pintype "input+no_connect"))
    )
    (net (code "209") (name "unconnected-(J1-CD-Pad9)") (class "Default")
      (node (ref "J1") (pin "9") (pinfunction "CD_9") (pintype "input+no_connect"))
    )
    (net (code "210") (name "unconnected-(J1-DAT1(RSV)-Pad8)") (class "Default")
      (node (ref "J1") (pin "8") (pinfunction "DAT1(RSV)_8") (pintype "bidirectional+no_connect"))
    )
    (net (code "211") (name "unconnected-(J1-DAT2(RSV)-Pad1)") (class "Default")
      (node (ref "J1") (pin "1") (pinfunction "DAT2(RSV)_1") (pintype "bidirectional+no_connect"))
    )
    (net (code "212") (name "unconnected-(J2-CC1-PadA5)") (class "Default")
      (node (ref "J2") (pin "A5") (pinfunction "CC1_A5") (pintype "unspecified+no_connect"))
    )
    (net (code "213") (name "unconnected-(J2-CC2-PadB5)") (class "Default")
      (node (ref "J2") (pin "B5") (pinfunction "CC2_B5") (pintype "unspecified+no_connect"))
    )
    (net (code "214") (name "unconnected-(J2-SBU1-PadA8)") (class "Default")
      (node (ref "J2") (pin "A8") (pinfunction "SBU1_A8") (pintype "unspecified+no_connect"))
    )
    (net (code "215") (name "unconnected-(J2-SBU2-PadB8)") (class "Default")
      (node (ref "J2") (pin "B8") (pinfunction "SBU2_B8") (pintype "unspecified+no_connect"))
    )
    (net (code "216") (name "unconnected-(LCD1-Pad3)") (class "Default")
      (node (ref "LCD1") (pin "3") (pinfunction "3_3") (pintype "input+no_connect"))
    )
    (net (code "217") (name "unconnected-(LCD1-Pad4)") (class "Default")
      (node (ref "LCD1") (pin "4") (pinfunction "4_4") (pintype "input+no_connect"))
    )
    (net (code "218") (name "unconnected-(LCD1-Pad5)") (class "Default")
      (node (ref "LCD1") (pin "5") (pinfunction "5_5") (pintype "input+no_connect"))
    )
    (net (code "219") (name "unconnected-(LCD1-Pad6)") (class "Default")
      (node (ref "LCD1") (pin "6") (pinfunction "6_6") (pintype "input+no_connect"))
    )
    (net (code "220") (name "unconnected-(LCD1-Pad7)") (class "Default")
      (node (ref "LCD1") (pin "7") (pinfunction "7_7") (pintype "input+no_connect"))
    )
    (net (code "221") (name "unconnected-(LCD1-Pad8)") (class "Default")
      (node (ref "LCD1") (pin "8") (pinfunction "8_8") (pintype "input+no_connect"))
    )
    (net (code "222") (name "unconnected-(T3-Pad1)") (class "Default")
      (node (ref "T3") (pin "1") (pinfunction "1_1") (pintype "unspecified+no_connect"))
    )
    (net (code "223") (name "unconnected-(T4-Pad1)") (class "Default")
      (node (ref "T4") (pin "1") (pinfunction "1_1") (pintype "unspecified+no_connect"))
    )
    (net (code "224") (name "unconnected-(T5-Pad1)") (class "Default")
      (node (ref "T5") (pin "1") (pinfunction "1_1") (pintype "unspecified+no_connect"))
    )
    (net (code "225") (name "unconnected-(T6-Pad1)") (class "Default")
      (node (ref "T6") (pin "1") (pinfunction "1_1") (pintype "unspecified+no_connect"))
    )
    (net (code "226") (name "unconnected-(U2-CLK-Pad17)") (class "Default")
      (node (ref "U2") (pin "17") (pinfunction "CLK_17") (pintype "unspecified+no_connect"))
    )
    (net (code "227") (name "unconnected-(U2-EP-Pad29)") (class "Default")
      (node (ref "U2") (pin "29") (pinfunction "EP_29") (pintype "unspecified+no_connect"))
    )
    (net (code "228") (name "unconnected-(U2-INDEX-Pad16)") (class "Default")
      (node (ref "U2") (pin "16") (pinfunction "INDEX_16") (pintype "unspecified+no_connect"))
    )
    (net (code "229") (name "unconnected-(U2-NC-Pad13)") (class "Default")
      (node (ref "U2") (pin "13") (pinfunction "NC_13") (pintype "unspecified+no_connect"))
    )
    (net (code "230") (name "unconnected-(U2-PDN_UART-Pad18)") (class "Default")
      (node (ref "U2") (pin "18") (pinfunction "PDN_UART_18") (pintype "unspecified+no_connect"))
    )
    (net (code "231") (name "unconnected-(U2-SPREAD-Pad10)") (class "Default")
      (node (ref "U2") (pin "10") (pinfunction "SPREAD_10") (pintype "unspecified+no_connect"))
    )
    (net (code "232") (name "unconnected-(U2-STDBY-Pad24)") (class "Default")
      (node (ref "U2") (pin "24") (pinfunction "STDBY_24") (pintype "unspecified+no_connect"))
    )
    (net (code "233") (name "unconnected-(U2-VREF-Pad21)") (class "Default")
      (node (ref "U2") (pin "21") (pinfunction "VREF_21") (pintype "unspecified+no_connect"))
    )
    (net (code "234") (name "unconnected-(U3-CLK-Pad20)") (class "Default")
      (node (ref "U3") (pin "20") (pinfunction "CLK_20") (pintype "unspecified+no_connect"))
    )
    (net (code "235") (name "unconnected-(U3-CMD-Pad19)") (class "Default")
      (node (ref "U3") (pin "19") (pinfunction "CMD_19") (pintype "unspecified+no_connect"))
    )
    (net (code "236") (name "unconnected-(U3-EP-Pad39)") (class "Default")
      (node (ref "U3") (pin "39") (pinfunction "EP_39") (pintype "unspecified+no_connect"))
    )
    (net (code "237") (name "unconnected-(U3-IO4-Pad26)") (class "Default")
      (node (ref "U3") (pin "26") (pinfunction "IO4_26") (pintype "unspecified+no_connect"))
    )
    (net (code "238") (name "unconnected-(U3-NC-Pad32)") (class "Default")
      (node (ref "U3") (pin "32") (pinfunction "NC_32") (pintype "unspecified+no_connect"))
    )
    (net (code "239") (name "unconnected-(U3-SD0-Pad21)") (class "Default")
      (node (ref "U3") (pin "21") (pinfunction "SD0_21") (pintype "unspecified+no_connect"))
    )
    (net (code "240") (name "unconnected-(U3-SD1-Pad22)") (class "Default")
      (node (ref "U3") (pin "22") (pinfunction "SD1_22") (pintype "unspecified+no_connect"))
    )
    (net (code "241") (name "unconnected-(U3-SD2-Pad17)") (class "Default")
      (node (ref "U3") (pin "17") (pinfunction "SD2_17") (pintype "unspecified+no_connect"))
    )
    (net (code "242") (name "unconnected-(U3-SD3-Pad18)") (class "Default")
      (node (ref "U3") (pin "18") (pinfunction "SD3_18") (pintype "unspecified+no_connect"))
    )
    (net (code "243") (name "unconnected-(U5-CTS#-Pad9)") (class "Default")
      (node (ref "U5") (pin "9") (pinfunction "CTS#_9") (pintype "unspecified+no_connect"))
    )
    (net (code "244") (name "unconnected-(U5-DCD#-Pad12)") (class "Default")
      (node (ref "U5") (pin "12") (pinfunction "DCD#_12") (pintype "unspecified+no_connect"))
    )
    (net (code "245") (name "unconnected-(U5-DSR#-Pad10)") (class "Default")
      (node (ref "U5") (pin "10") (pinfunction "DSR#_10") (pintype "unspecified+no_connect"))
    )
    (net (code "246") (name "unconnected-(U5-NC.-Pad7)") (class "Default")
      (node (ref "U5") (pin "7") (pinfunction "NC._7") (pintype "unspecified+no_connect"))
    )
    (net (code "247") (name "unconnected-(U5-NC.-Pad8)") (class "Default")
      (node (ref "U5") (pin "8") (pinfunction "NC._8") (pintype "unspecified+no_connect"))
    )
    (net (code "248") (name "unconnected-(U5-R232-Pad15)") (class "Default")
      (node (ref "U5") (pin "15") (pinfunction "R232_15") (pintype "unspecified+no_connect"))
    )
    (net (code "249") (name "unconnected-(U5-RI#-Pad11)") (class "Default")
      (node (ref "U5") (pin "11") (pinfunction "RI#_11") (pintype "unspecified+no_connect"))
    )
    (net (code "250") (name "unconnected-(U7-Q2-Pad2)") (class "Default")
      (node (ref "U7") (pin "2") (pinfunction "Q2_2") (pintype "unspecified+no_connect"))
    )
    (net (code "251") (name "unconnected-(U7-Q3-Pad3)") (class "Default")
      (node (ref "U7") (pin "3") (pinfunction "Q3_3") (pintype "unspecified+no_connect"))
    )
    (net (code "252") (name "unconnected-(U7-Q4-Pad4)") (class "Default")
      (node (ref "U7") (pin "4") (pinfunction "Q4_4") (pintype "unspecified+no_connect"))
    )
    (net (code "253") (name "unconnected-(U7-Q7S-Pad9)") (class "Default")
      (node (ref "U7") (pin "9") (pinfunction "Q7S_9") (pintype "unspecified+no_connect"))
    )
    (net (code "254") (name "unconnected-(U8-CLK-Pad17)") (class "Default")
      (node (ref "U8") (pin "17") (pinfunction "CLK_17") (pintype "unspecified+no_connect"))
    )
    (net (code "255") (name "unconnected-(U8-EP-Pad29)") (class "Default")
      (node (ref "U8") (pin "29") (pinfunction "EP_29") (pintype "unspecified+no_connect"))
    )
    (net (code "256") (name "unconnected-(U8-INDEX-Pad16)") (class "Default")
      (node (ref "U8") (pin "16") (pinfunction "INDEX_16") (pintype "unspecified+no_connect"))
    )
    (net (code "257") (name "unconnected-(U8-NC-Pad13)") (class "Default")
      (node (ref "U8") (pin "13") (pinfunction "NC_13") (pintype "unspecified+no_connect"))
    )
    (net (code "258") (name "unconnected-(U8-PDN_UART-Pad18)") (class "Default")
      (node (ref "U8") (pin "18") (pinfunction "PDN_UART_18") (pintype "unspecified+no_connect"))
    )
    (net (code "259") (name "unconnected-(U8-SPREAD-Pad10)") (class "Default")
      (node (ref "U8") (pin "10") (pinfunction "SPREAD_10") (pintype "unspecified+no_connect"))
    )
    (net (code "260") (name "unconnected-(U8-STDBY-Pad24)") (class "Default")
      (node (ref "U8") (pin "24") (pinfunction "STDBY_24") (pintype "unspecified+no_connect"))
    )
    (net (code "261") (name "unconnected-(U8-VREF-Pad21)") (class "Default")
      (node (ref "U8") (pin "21") (pinfunction "VREF_21") (pintype "unspecified+no_connect"))
    )
    (net (code "262") (name "unconnected-(U9-CLK-Pad17)") (class "Default")
      (node (ref "U9") (pin "17") (pinfunction "CLK_17") (pintype "unspecified+no_connect"))
    )
    (net (code "263") (name "unconnected-(U9-EP-Pad29)") (class "Default")
      (node (ref "U9") (pin "29") (pinfunction "EP_29") (pintype "unspecified+no_connect"))
    )
    (net (code "264") (name "unconnected-(U9-INDEX-Pad16)") (class "Default")
      (node (ref "U9") (pin "16") (pinfunction "INDEX_16") (pintype "unspecified+no_connect"))
    )
    (net (code "265") (name "unconnected-(U9-NC-Pad13)") (class "Default")
      (node (ref "U9") (pin "13") (pinfunction "NC_13") (pintype "unspecified+no_connect"))
    )
    (net (code "266") (name "unconnected-(U9-PDN_UART-Pad18)") (class "Default")
      (node (ref "U9") (pin "18") (pinfunction "PDN_UART_18") (pintype "unspecified+no_connect"))
    )
    (net (code "267") (name "unconnected-(U9-SPREAD-Pad10)") (class "Default")
      (node (ref "U9") (pin "10") (pinfunction "SPREAD_10") (pintype "unspecified+no_connect"))
    )
    (net (code "268") (name "unconnected-(U9-STDBY-Pad24)") (class "Default")
      (node (ref "U9") (pin "24") (pinfunction "STDBY_24") (pintype "unspecified+no_connect"))
    )
    (net (code "269") (name "unconnected-(U9-VREF-Pad21)") (class "Default")
      (node (ref "U9") (pin "21") (pinfunction "VREF_21") (pintype "unspecified+no_connect"))
    )
    (net (code "270") (name "unconnected-(U11-CLK-Pad17)") (class "Default")
      (node (ref "U11") (pin "17") (pinfunction "CLK_17") (pintype "unspecified+no_connect"))
    )
    (net (code "271") (name "unconnected-(U11-EP-Pad29)") (class "Default")
      (node (ref "U11") (pin "29") (pinfunction "EP_29") (pintype "unspecified+no_connect"))
    )
    (net (code "272") (name "unconnected-(U11-INDEX-Pad16)") (class "Default")
      (node (ref "U11") (pin "16") (pinfunction "INDEX_16") (pintype "unspecified+no_connect"))
    )
    (net (code "273") (name "unconnected-(U11-NC-Pad13)") (class "Default")
      (node (ref "U11") (pin "13") (pinfunction "NC_13") (pintype "unspecified+no_connect"))
    )
    (net (code "274") (name "unconnected-(U11-SPREAD-Pad10)") (class "Default")
      (node (ref "U11") (pin "10") (pinfunction "SPREAD_10") (pintype "unspecified+no_connect"))
    )
    (net (code "275") (name "unconnected-(U11-STDBY-Pad24)") (class "Default")
      (node (ref "U11") (pin "24") (pinfunction "STDBY_24") (pintype "unspecified+no_connect"))
    )
    (net (code "276") (name "unconnected-(U11-VREF-Pad21)") (class "Default")
      (node (ref "U11") (pin "21") (pinfunction "VREF_21") (pintype "unspecified+no_connect"))
    )
    (net (code "277") (name "unconnected-(U12-CLK-Pad17)") (class "Default")
      (node (ref "U12") (pin "17") (pinfunction "CLK_17") (pintype "unspecified+no_connect"))
    )
    (net (code "278") (name "unconnected-(U12-EP-Pad29)") (class "Default")
      (node (ref "U12") (pin "29") (pinfunction "EP_29") (pintype "unspecified+no_connect"))
    )
    (net (code "279") (name "unconnected-(U12-INDEX-Pad16)") (class "Default")
      (node (ref "U12") (pin "16") (pinfunction "INDEX_16") (pintype "unspecified+no_connect"))
    )
    (net (code "280") (name "unconnected-(U12-NC-Pad13)") (class "Default")
      (node (ref "U12") (pin "13") (pinfunction "NC_13") (pintype "unspecified+no_connect"))
    )
    (net (code "281") (name "unconnected-(U12-SPREAD-Pad10)") (class "Default")
      (node (ref "U12") (pin "10") (pinfunction "SPREAD_10") (pintype "unspecified+no_connect"))
    )
    (net (code "282") (name "unconnected-(U12-STDBY-Pad24)") (class "Default")
      (node (ref "U12") (pin "24") (pinfunction "STDBY_24") (pintype "unspecified+no_connect"))
    )
    (net (code "283") (name "unconnected-(U12-VREF-Pad21)") (class "Default")
      (node (ref "U12") (pin "21") (pinfunction "VREF_21") (pintype "unspecified+no_connect"))
    )
    (net (code "284") (name "unconnected-(U13-CLK-Pad17)") (class "Default")
      (node (ref "U13") (pin "17") (pinfunction "CLK_17") (pintype "unspecified+no_connect"))
    )
    (net (code "285") (name "unconnected-(U13-EP-Pad29)") (class "Default")
      (node (ref "U13") (pin "29") (pinfunction "EP_29") (pintype "unspecified+no_connect"))
    )
    (net (code "286") (name "unconnected-(U13-INDEX-Pad16)") (class "Default")
      (node (ref "U13") (pin "16") (pinfunction "INDEX_16") (pintype "unspecified+no_connect"))
    )
    (net (code "287") (name "unconnected-(U13-NC-Pad13)") (class "Default")
      (node (ref "U13") (pin "13") (pinfunction "NC_13") (pintype "unspecified+no_connect"))
    )
    (net (code "288") (name "unconnected-(U13-SPREAD-Pad10)") (class "Default")
      (node (ref "U13") (pin "10") (pinfunction "SPREAD_10") (pintype "unspecified+no_connect"))
    )
    (net (code "289") (name "unconnected-(U13-STDBY-Pad24)") (class "Default")
      (node (ref "U13") (pin "24") (pinfunction "STDBY_24") (pintype "unspecified+no_connect"))
    )
    (net (code "290") (name "unconnected-(U13-VREF-Pad21)") (class "Default")
      (node (ref "U13") (pin "21") (pinfunction "VREF_21") (pintype "unspecified+no_connect"))
    )
    (net (code "291") (name "unconnected-(U14-CLK-Pad17)") (class "Default")
      (node (ref "U14") (pin "17") (pinfunction "CLK_17") (pintype "unspecified+no_connect"))
    )
    (net (code "292") (name "unconnected-(U14-EP-Pad29)") (class "Default")
      (node (ref "U14") (pin "29") (pinfunction "EP_29") (pintype "unspecified+no_connect"))
    )
    (net (code "293") (name "unconnected-(U14-INDEX-Pad16)") (class "Default")
      (node (ref "U14") (pin "16") (pinfunction "INDEX_16") (pintype "unspecified+no_connect"))
    )
    (net (code "294") (name "unconnected-(U14-NC-Pad13)") (class "Default")
      (node (ref "U14") (pin "13") (pinfunction "NC_13") (pintype "unspecified+no_connect"))
    )
    (net (code "295") (name "unconnected-(U14-SPREAD-Pad10)") (class "Default")
      (node (ref "U14") (pin "10") (pinfunction "SPREAD_10") (pintype "unspecified+no_connect"))
    )
    (net (code "296") (name "unconnected-(U14-STDBY-Pad24)") (class "Default")
      (node (ref "U14") (pin "24") (pinfunction "STDBY_24") (pintype "unspecified+no_connect"))
    )
    (net (code "297") (name "unconnected-(U14-VREF-Pad21)") (class "Default")
      (node (ref "U14") (pin "21") (pinfunction "VREF_21") (pintype "unspecified+no_connect"))
    )
    (net (code "298") (name "unconnected-(U15-CLK-Pad17)") (class "Default")
      (node (ref "U15") (pin "17") (pinfunction "CLK_17") (pintype "unspecified+no_connect"))
    )
    (net (code "299") (name "unconnected-(U15-EP-Pad29)") (class "Default")
      (node (ref "U15") (pin "29") (pinfunction "EP_29") (pintype "unspecified+no_connect"))
    )
    (net (code "300") (name "unconnected-(U15-INDEX-Pad16)") (class "Default")
      (node (ref "U15") (pin "16") (pinfunction "INDEX_16") (pintype "unspecified+no_connect"))
    )
    (net (code "301") (name "unconnected-(U15-NC-Pad13)") (class "Default")
      (node (ref "U15") (pin "13") (pinfunction "NC_13") (pintype "unspecified+no_connect"))
    )
    (net (code "302") (name "unconnected-(U15-PDN_UART-Pad18)") (class "Default")
      (node (ref "U15") (pin "18") (pinfunction "PDN_UART_18") (pintype "unspecified+no_connect"))
    )
    (net (code "303") (name "unconnected-(U15-SPREAD-Pad10)") (class "Default")
      (node (ref "U15") (pin "10") (pinfunction "SPREAD_10") (pintype "unspecified+no_connect"))
    )
    (net (code "304") (name "unconnected-(U15-STDBY-Pad24)") (class "Default")
      (node (ref "U15") (pin "24") (pinfunction "STDBY_24") (pintype "unspecified+no_connect"))
    )
    (net (code "305") (name "unconnected-(U15-VREF-Pad21)") (class "Default")
      (node (ref "U15") (pin "21") (pinfunction "VREF_21") (pintype "unspecified+no_connect"))
    )
  )
)
